# HDMI_RGB_LVDS.net
KiCad netlist of a schematic drawn in EAGLE
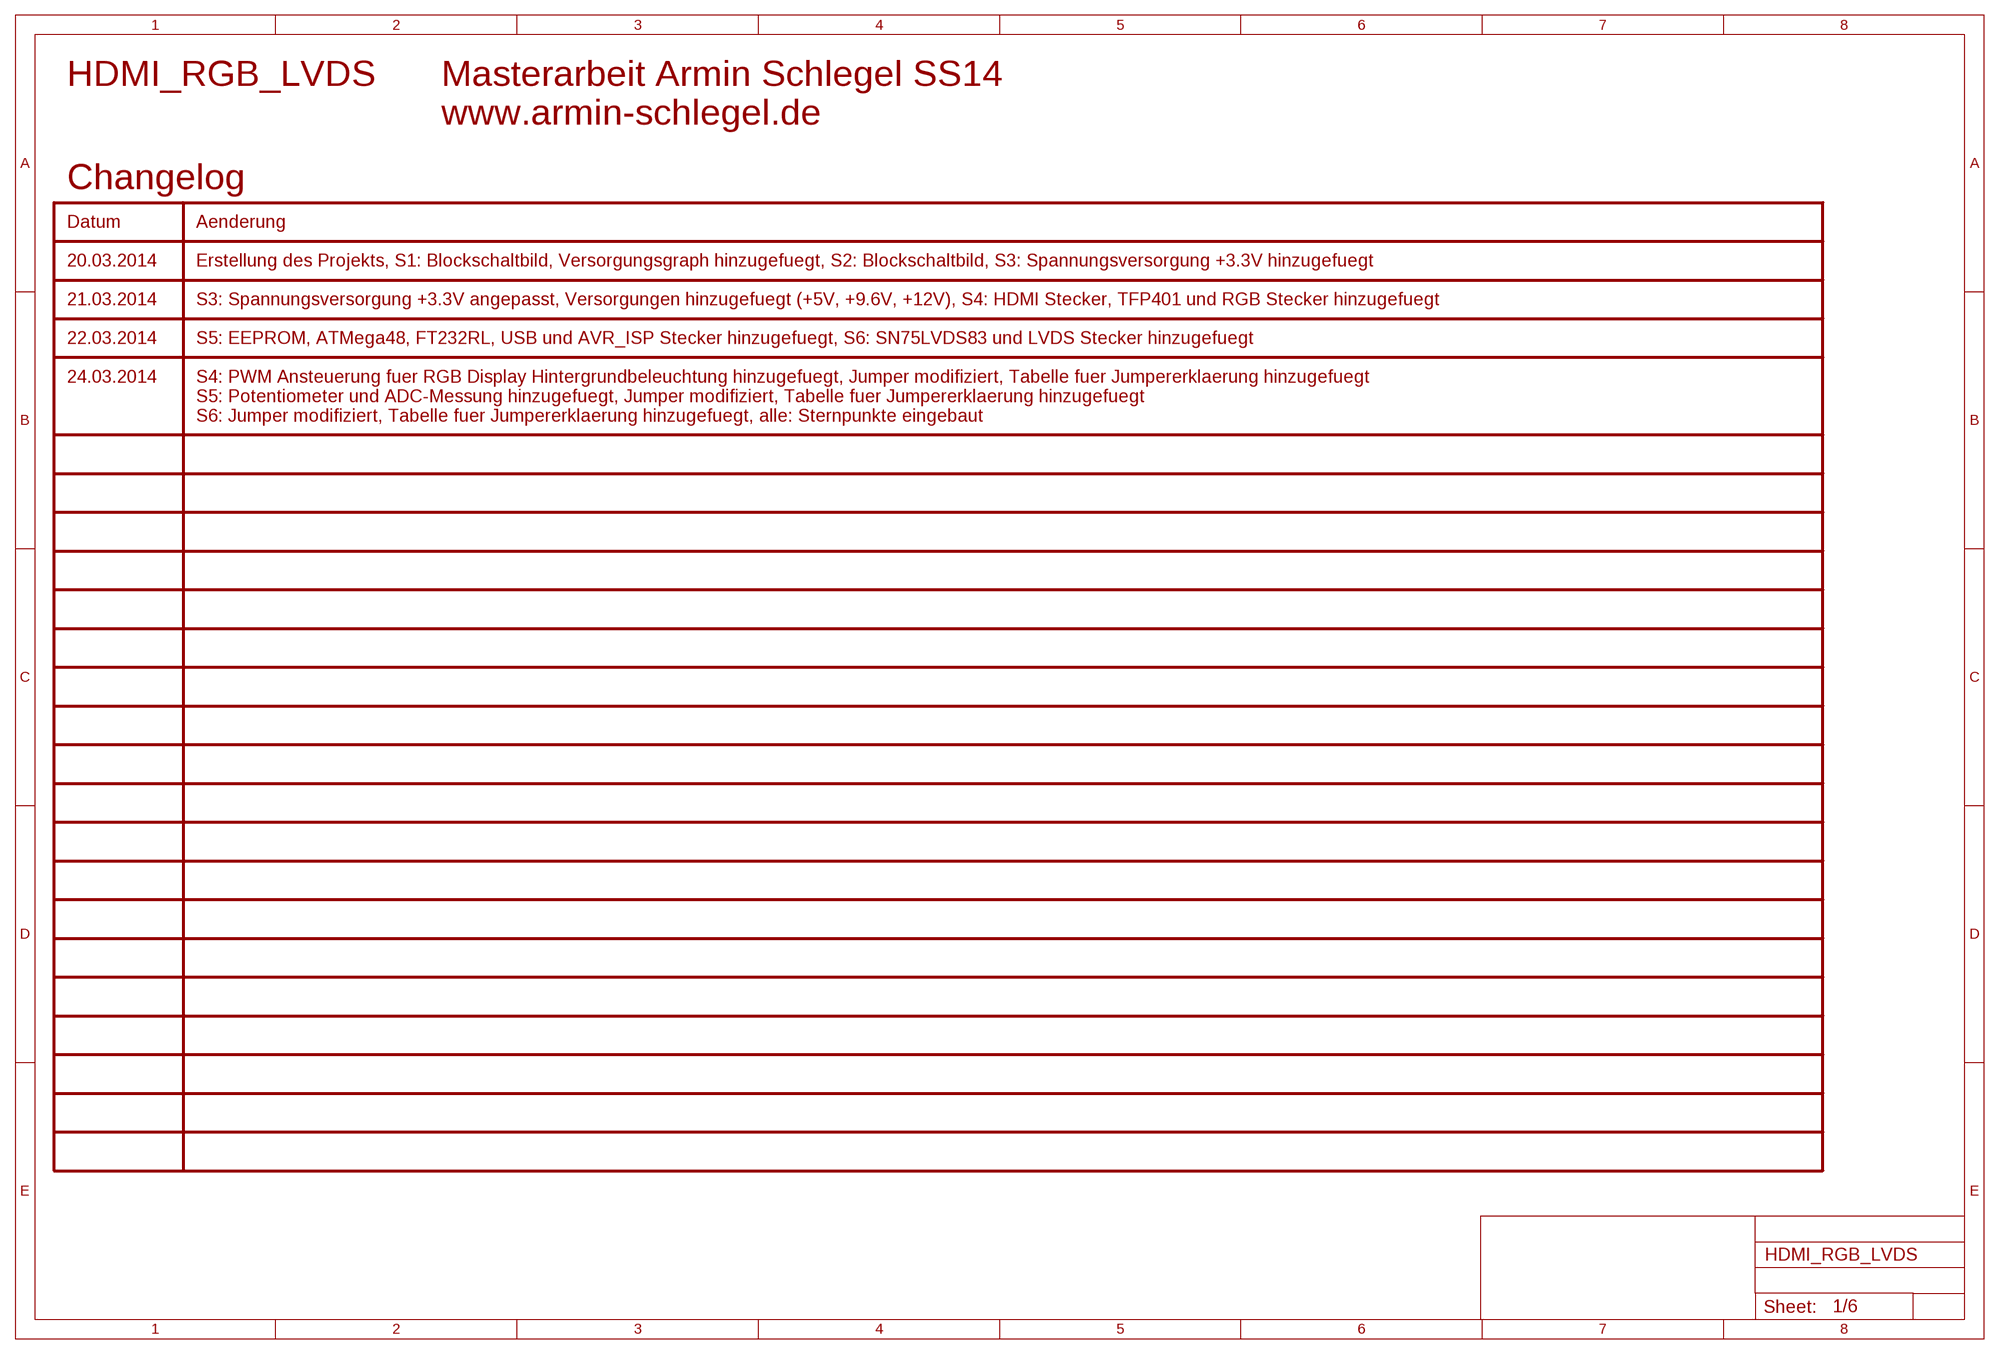
[diagram p0: schematic, sheet 1]
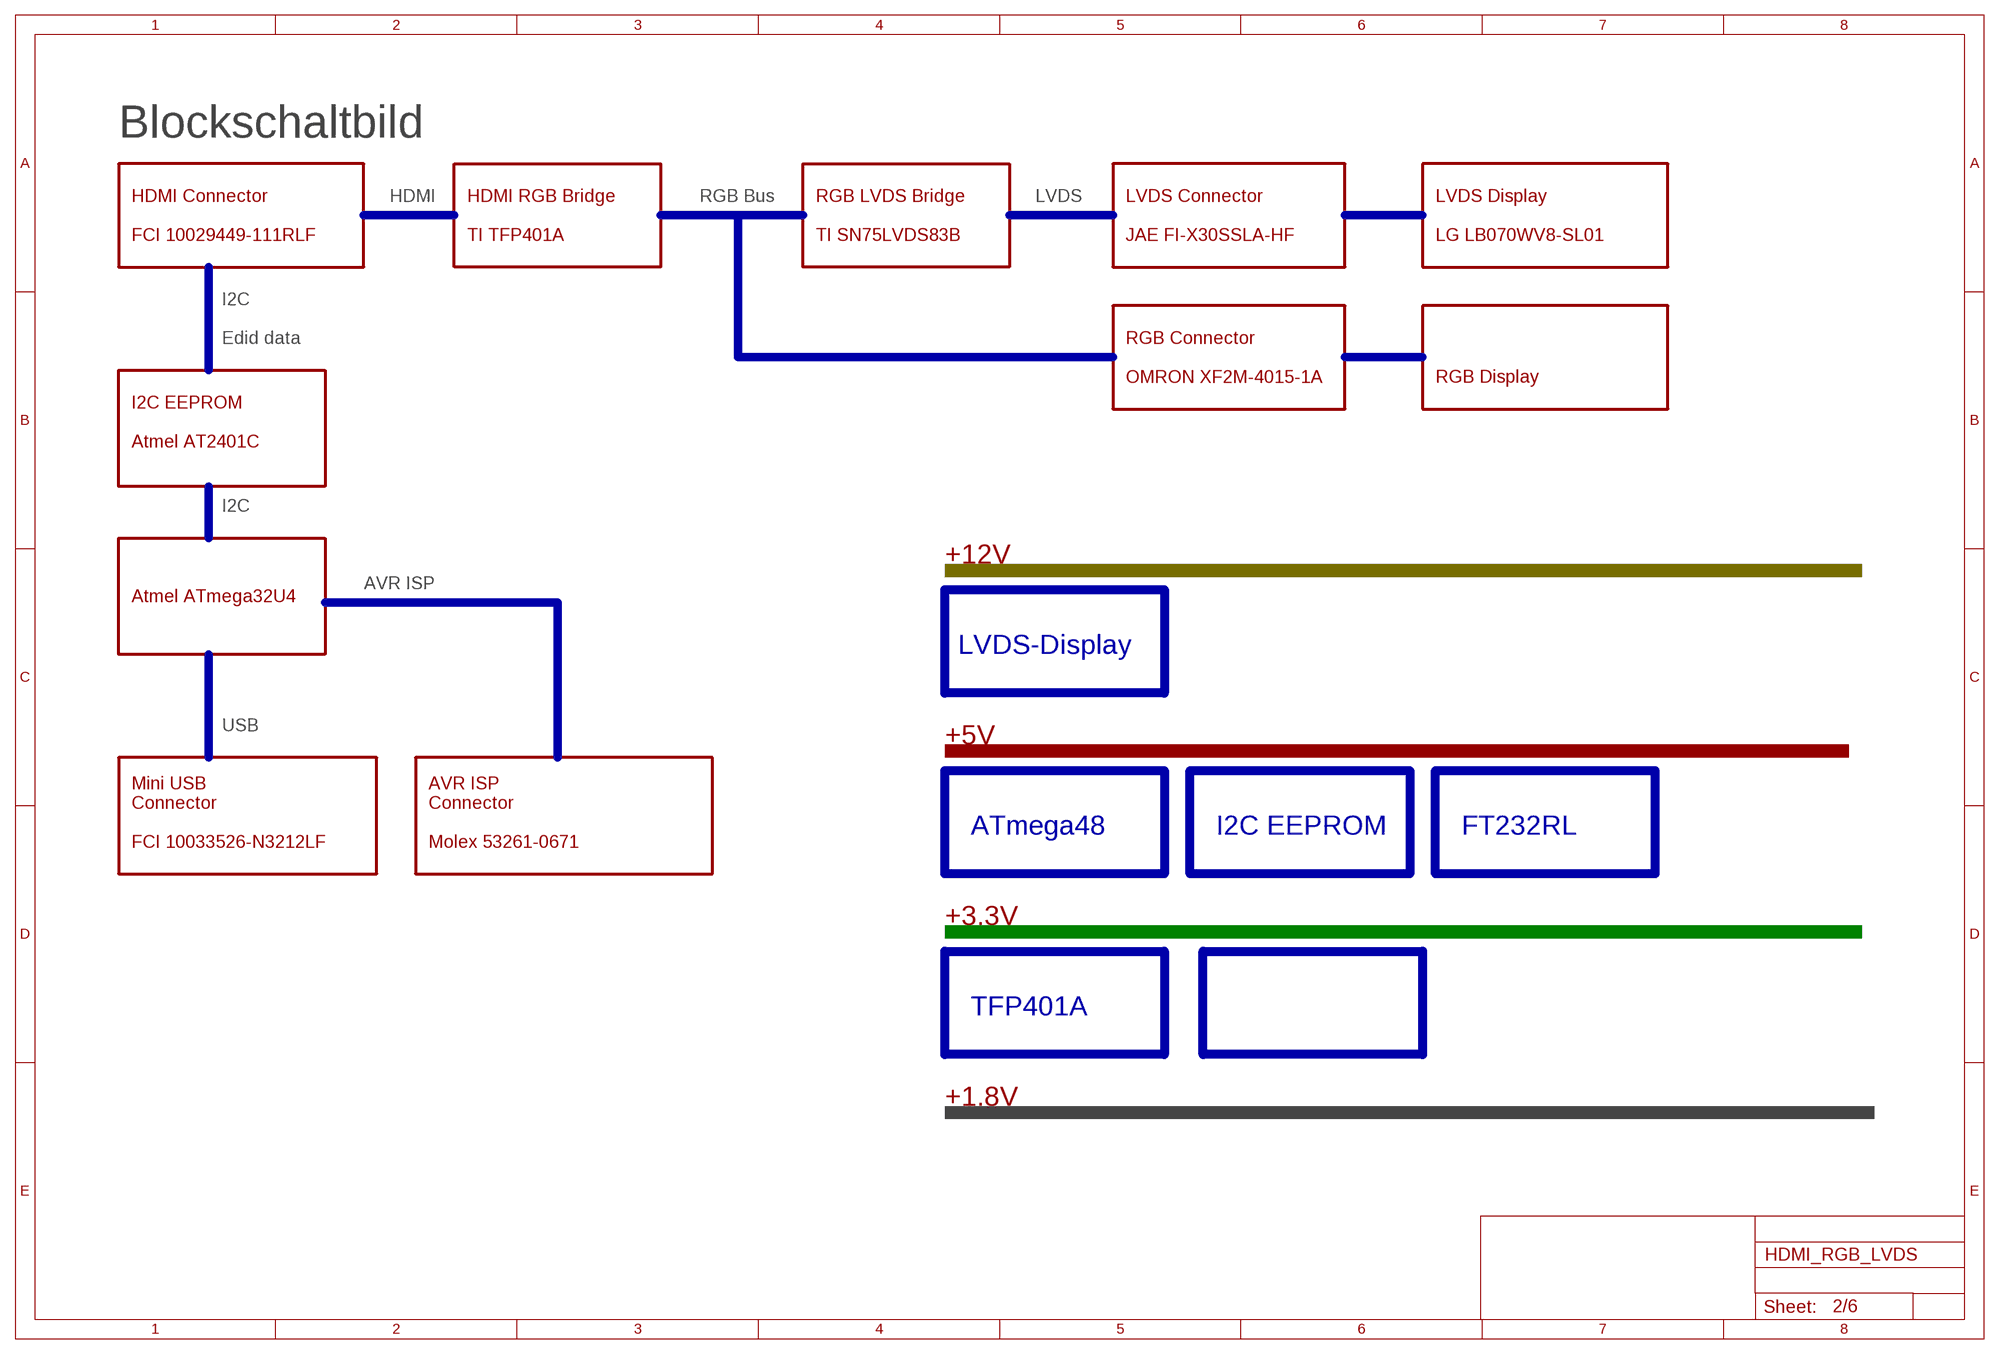
[diagram p1: schematic, sheet 2]
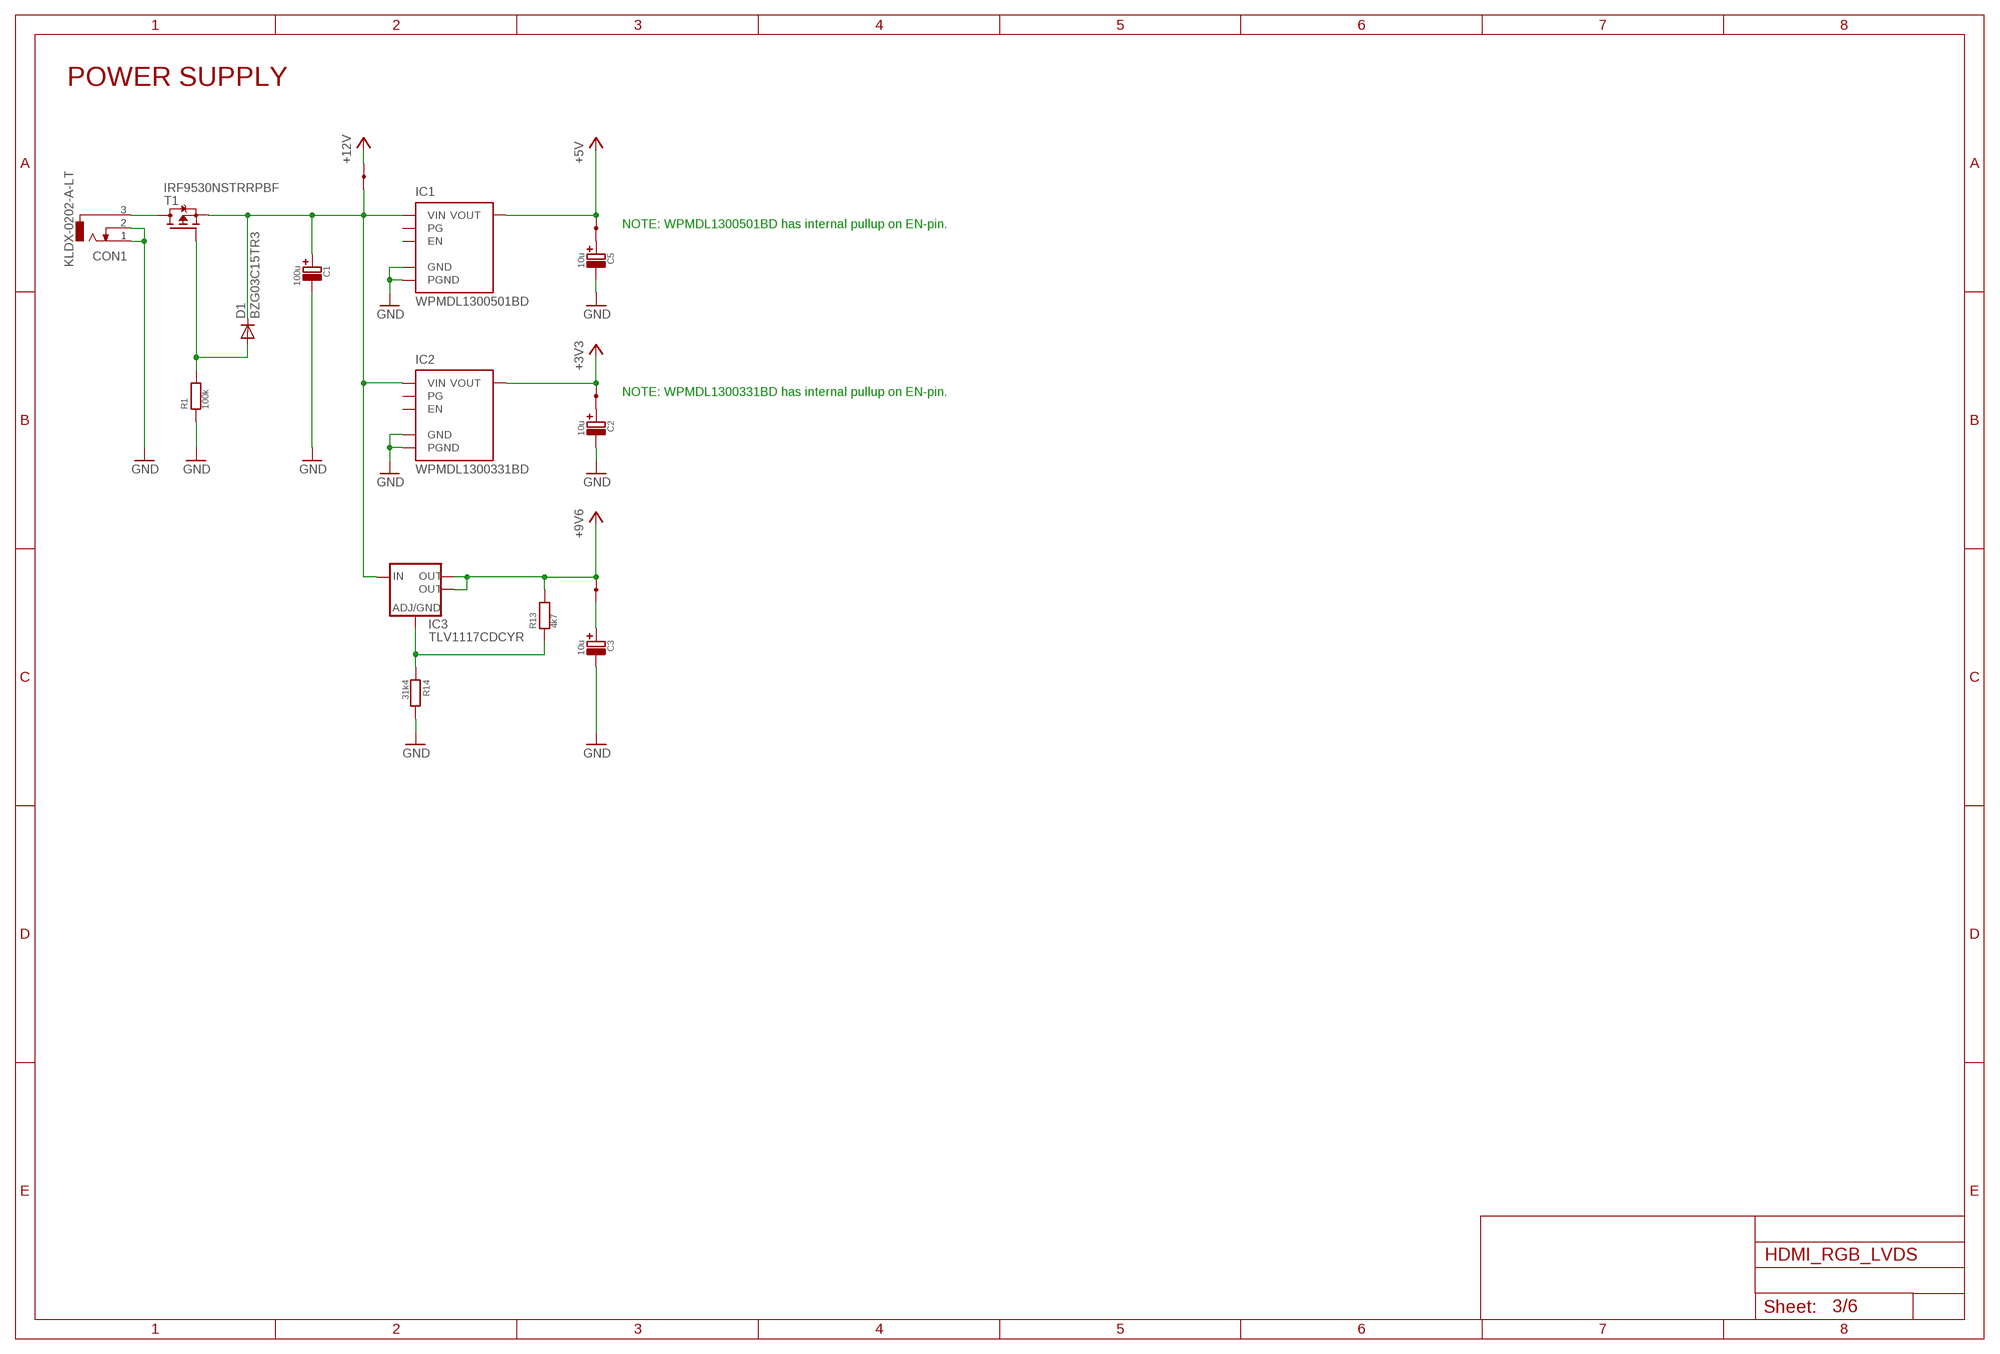
[diagram p2: schematic, sheet 3]
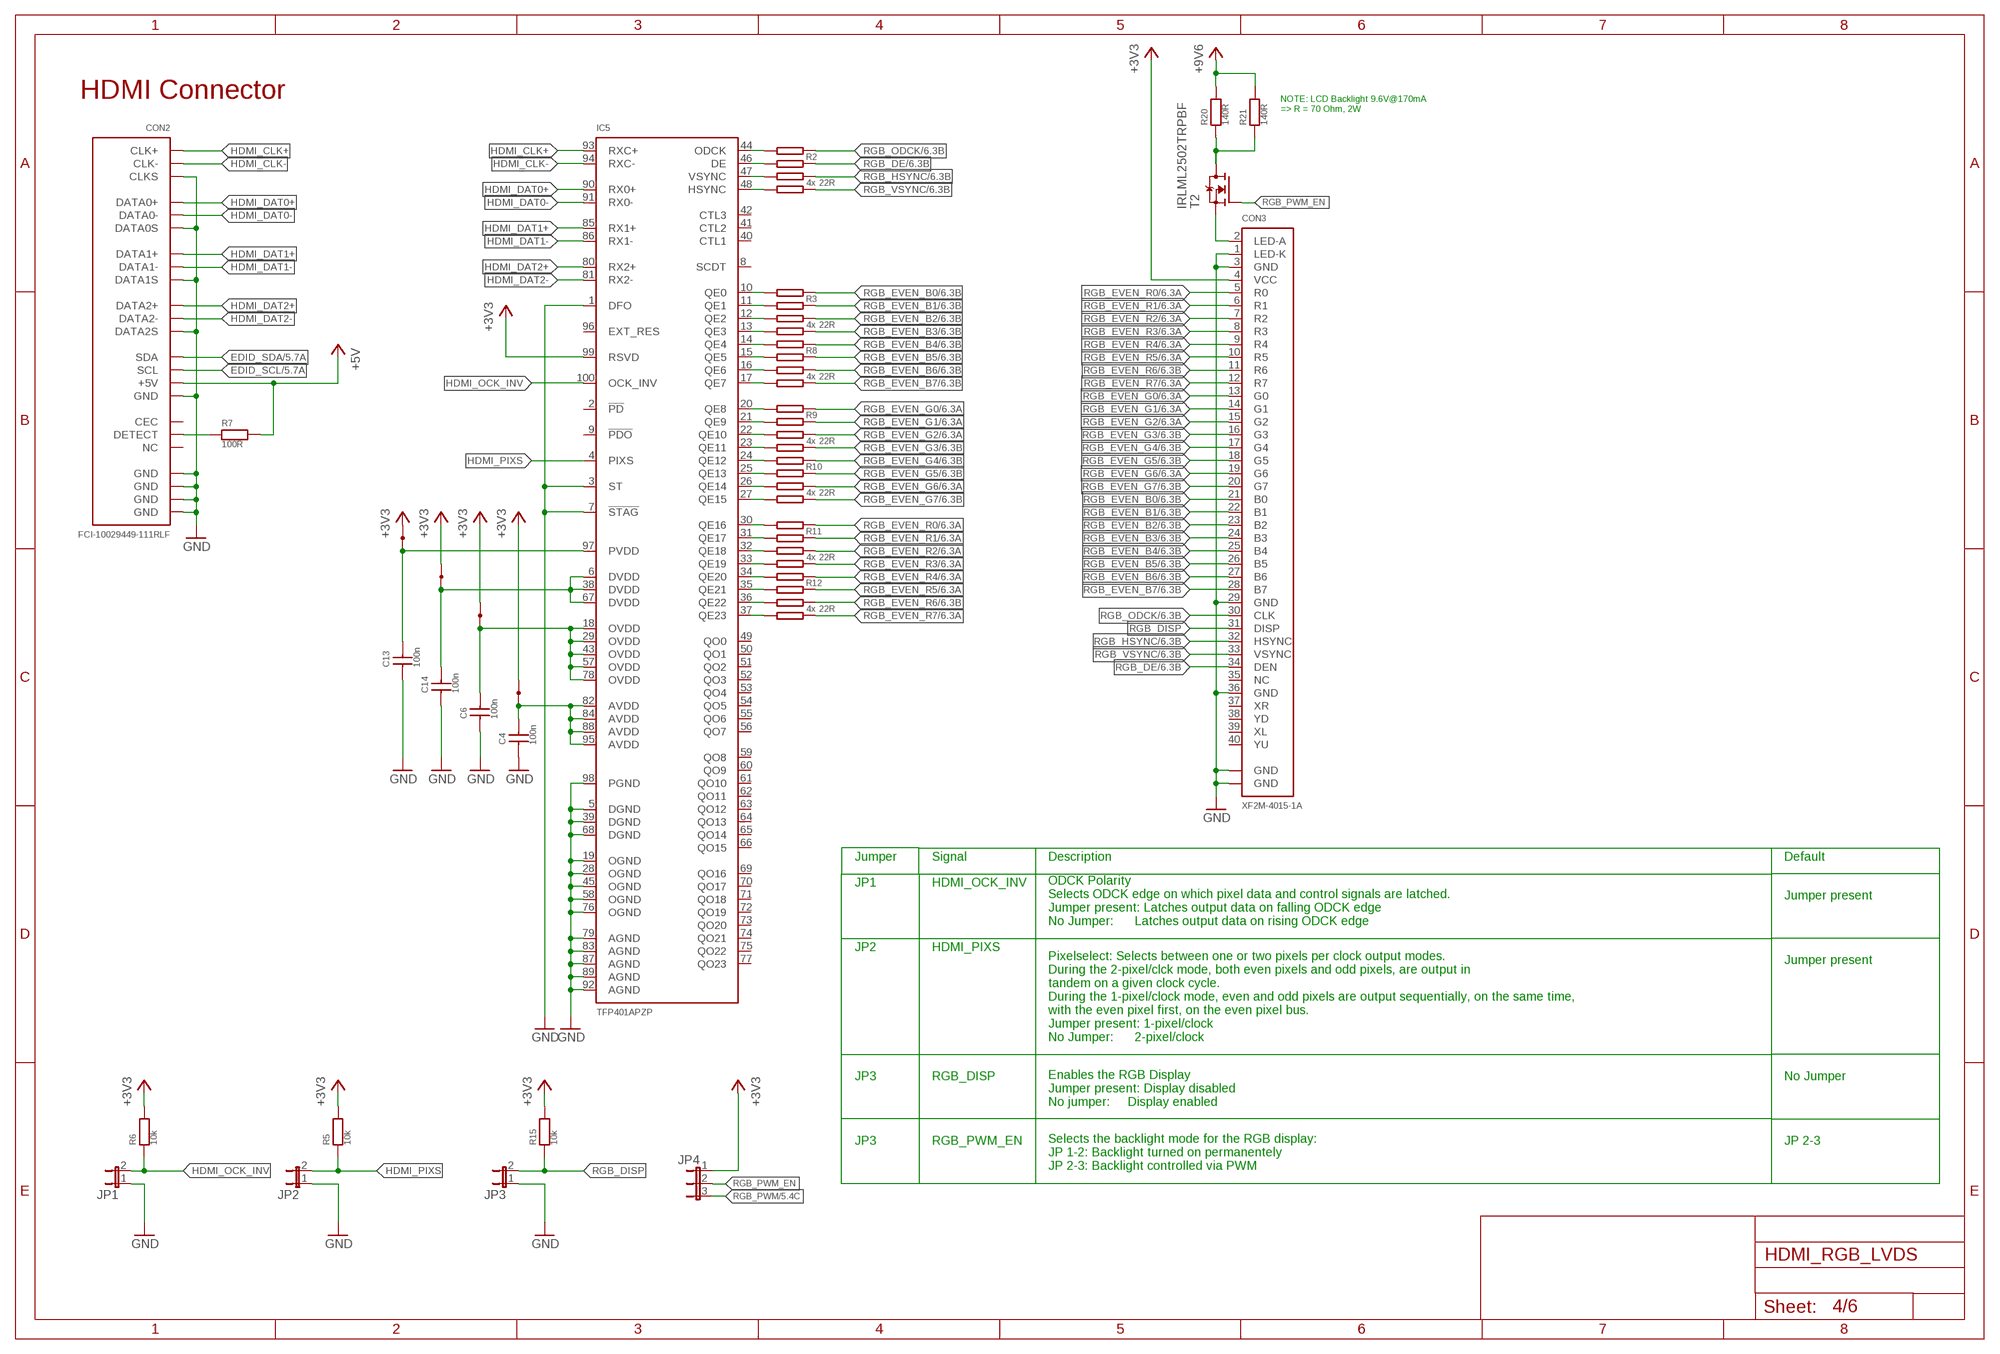
[diagram p3: schematic, sheet 4]
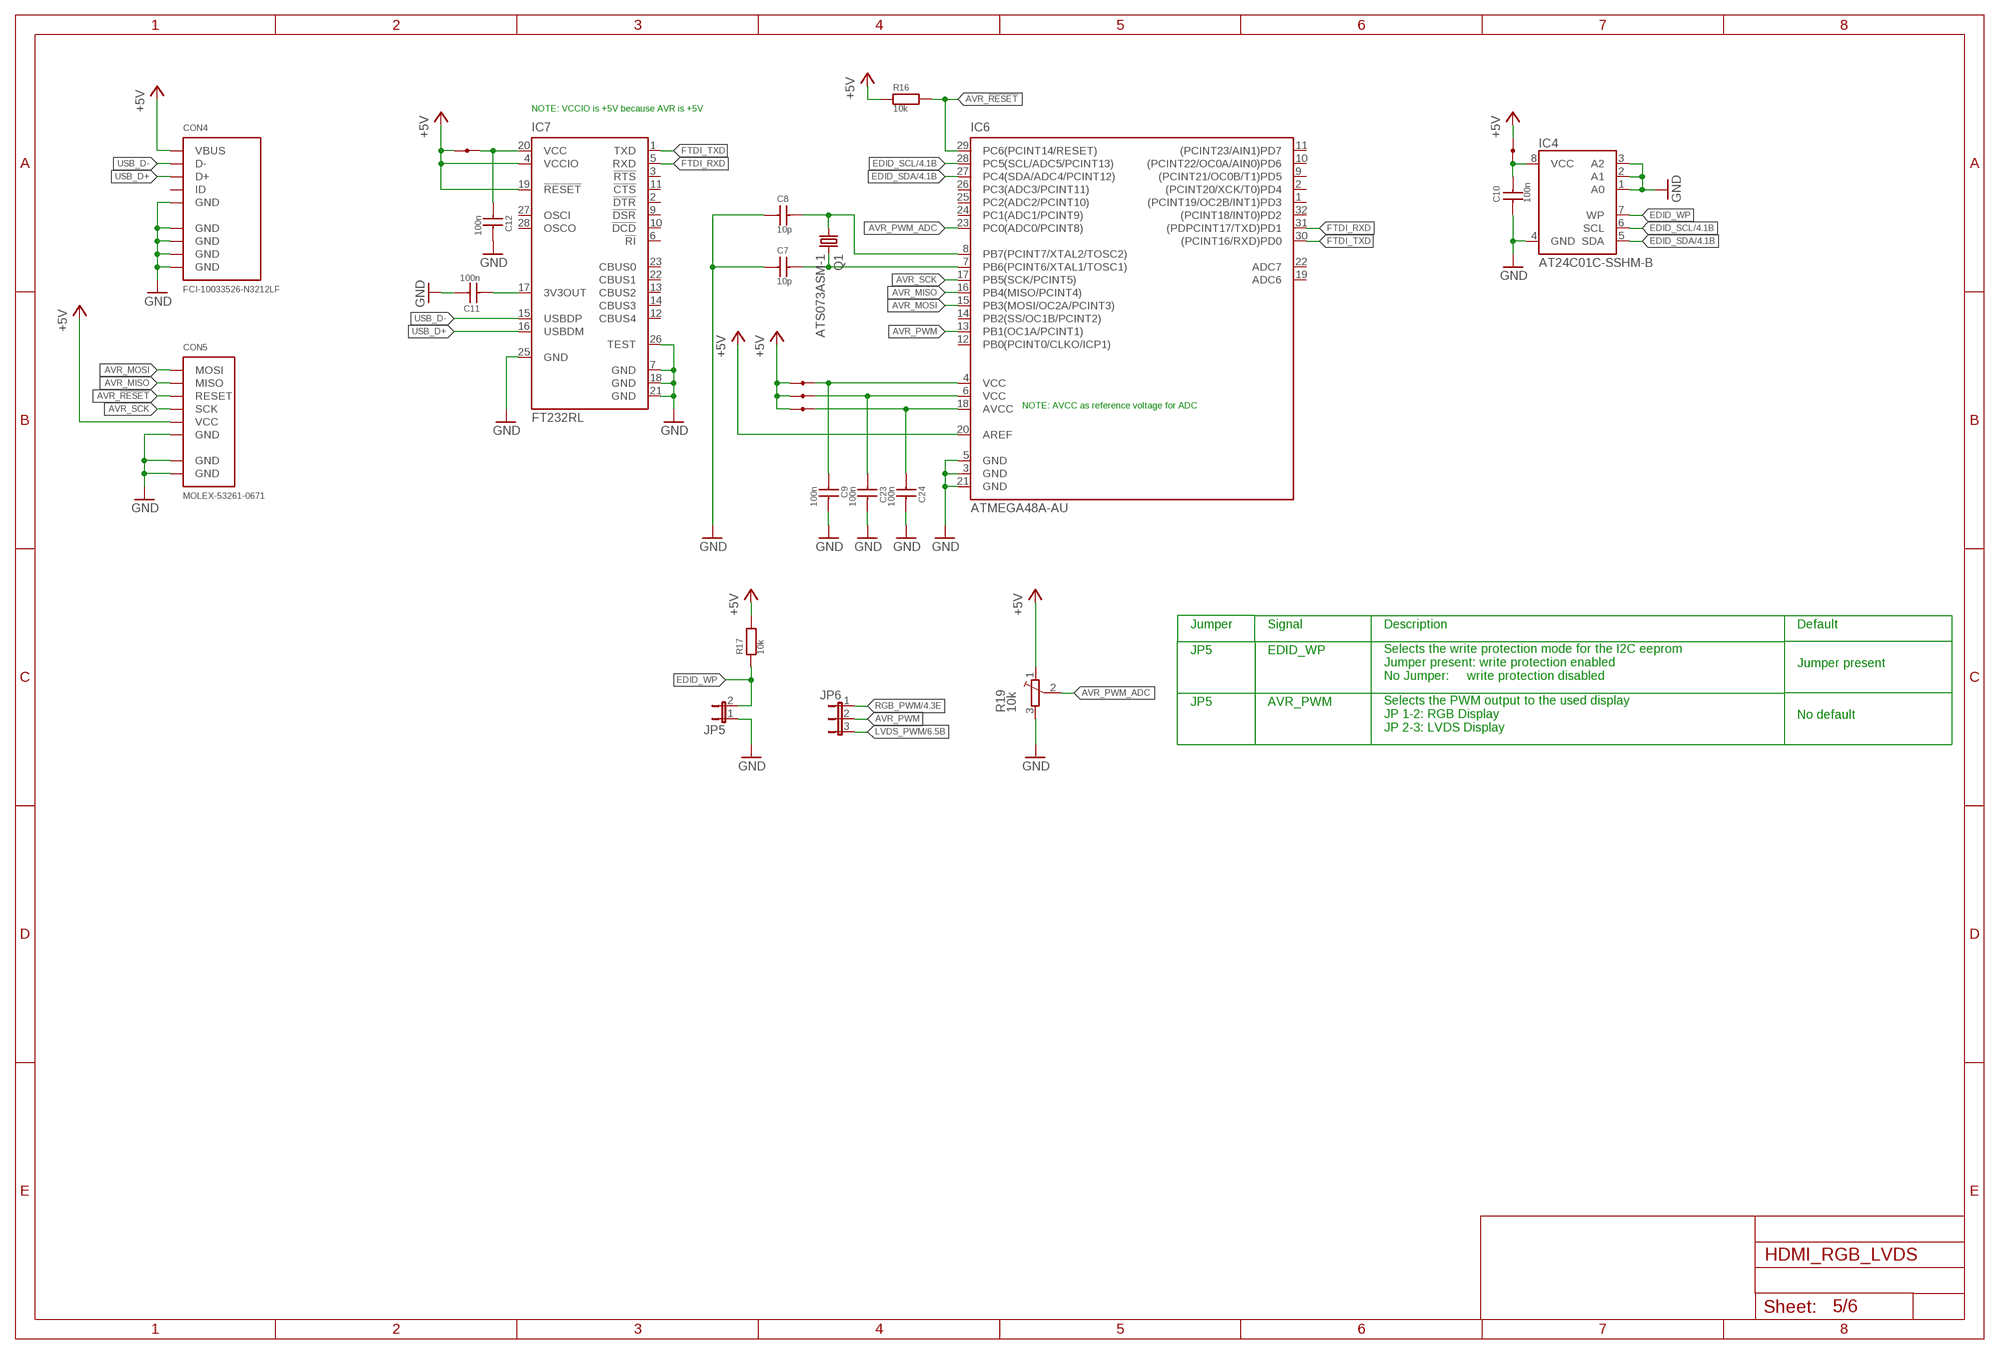
[diagram p4: schematic, sheet 5]
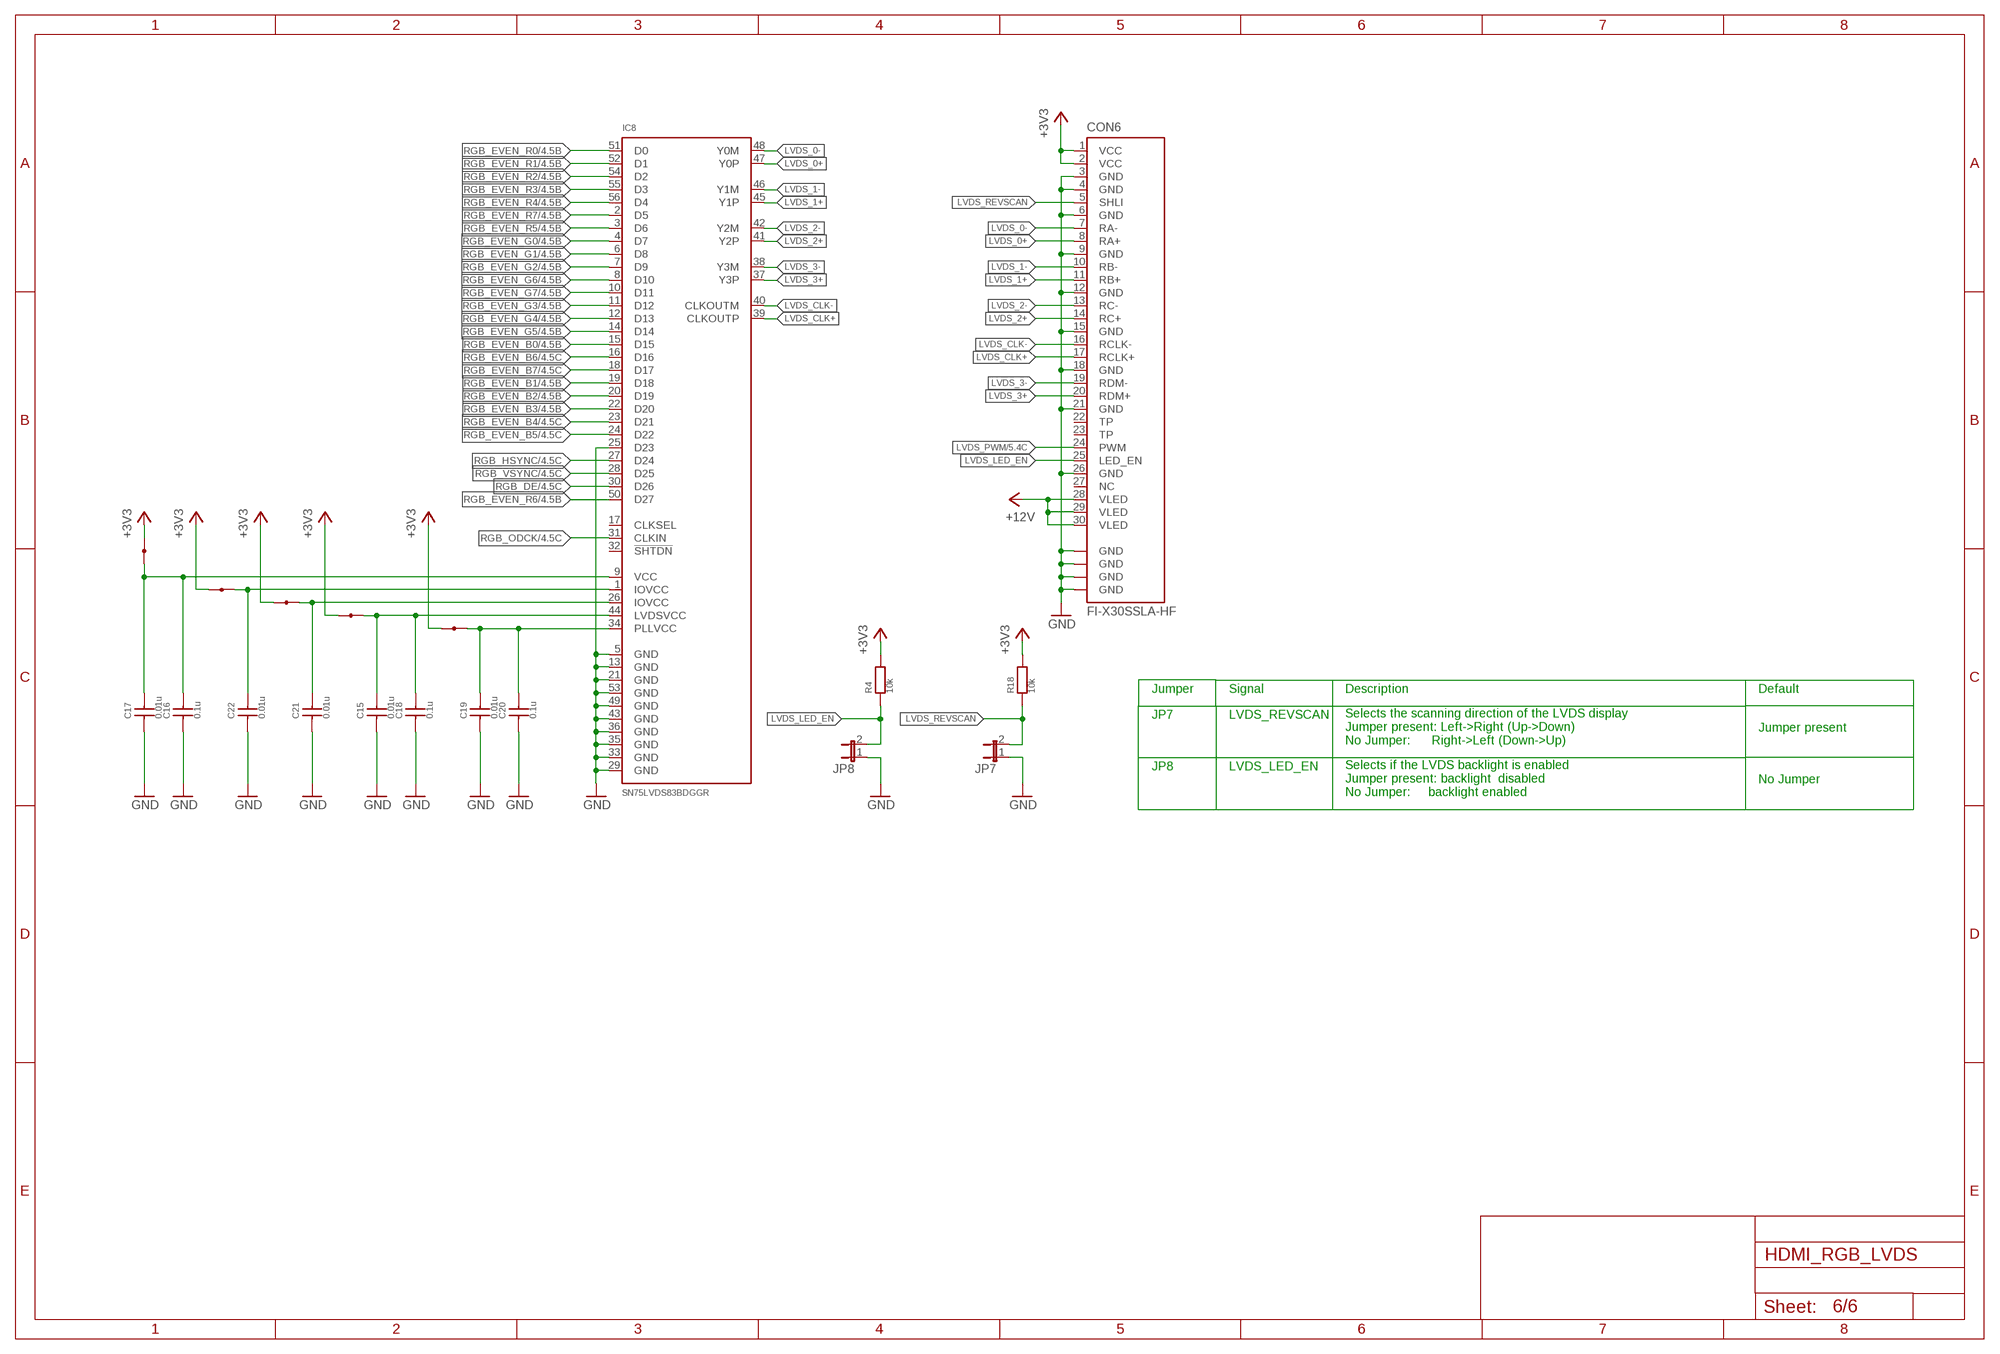
[diagram p5: schematic, sheet 6]

(export (version "E")
  (design (tool "Eeschema 10.0.6"))
  (components
    (comp (ref "U$15")
      (value "FRAME_A3_LANDSCAPE")
      (footprint "eagle-import:FRAME")
      (libsource (lib "eagle-import") (part "FRAME_A3_LANDSCAPE"))
    )
    (comp (ref "C15")
      (value "0.01u")
      (footprint "eagle-import:C0402")
      (libsource (lib "eagle-import") (part "C_SMD0402"))
    )
    (comp (ref "C16")
      (value "0.1u")
      (footprint "eagle-import:C0402")
      (libsource (lib "eagle-import") (part "C_SMD0402"))
    )
    (comp (ref "C17")
      (value "0.01u")
      (footprint "eagle-import:C0402")
      (libsource (lib "eagle-import") (part "C_SMD0402"))
    )
    (comp (ref "C18")
      (value "0.1u")
      (footprint "eagle-import:C0402")
      (libsource (lib "eagle-import") (part "C_SMD0402"))
    )
    (comp (ref "C19")
      (value "0.01u")
      (footprint "eagle-import:C0402")
      (libsource (lib "eagle-import") (part "C_SMD0402"))
    )
    (comp (ref "C20")
      (value "0.1u")
      (footprint "eagle-import:C0402")
      (libsource (lib "eagle-import") (part "C_SMD0402"))
    )
    (comp (ref "C21")
      (value "0.01u")
      (footprint "eagle-import:C0402")
      (libsource (lib "eagle-import") (part "C_SMD0402"))
    )
    (comp (ref "C22")
      (value "0.01u")
      (footprint "eagle-import:C0402")
      (libsource (lib "eagle-import") (part "C_SMD0402"))
    )
    (comp (ref "CON6")
      (value "FI-X30SSLA-HF")
      (footprint "eagle-import:FI-X30SSLA-HF")
      (libsource (lib "eagle-import") (part "FI-X30SSLA-HF"))
    )
    (comp (ref "IC8")
      (value "SN75LVDS83BDGGR")
      (footprint "eagle-import:TSSOP-56")
      (libsource (lib "eagle-import") (part "SN75LVDS83BDGGR"))
    )
    (comp (ref "JP7")
      (value "JUMPER2")
      (footprint "eagle-import:JUMPER2_THROUGHHOLE")
      (libsource (lib "eagle-import") (part "JUMPER2"))
    )
    (comp (ref "JP8")
      (value "JUMPER2")
      (footprint "eagle-import:JUMPER2_THROUGHHOLE")
      (libsource (lib "eagle-import") (part "JUMPER2"))
    )
    (comp (ref "R4")
      (value "10k")
      (footprint "eagle-import:R0402")
      (libsource (lib "eagle-import") (part "R0402"))
    )
    (comp (ref "R18")
      (value "10k")
      (footprint "eagle-import:R0402")
      (libsource (lib "eagle-import") (part "R0402"))
    )
    (comp (ref "SP14")
      (value "SP2")
      (footprint "eagle-import:SP2")
      (libsource (lib "eagle-import") (part "SP2"))
    )
    (comp (ref "SP15")
      (value "SP2")
      (footprint "eagle-import:SP2")
      (libsource (lib "eagle-import") (part "SP2"))
    )
    (comp (ref "SP16")
      (value "SP2")
      (footprint "eagle-import:SP2")
      (libsource (lib "eagle-import") (part "SP2"))
    )
    (comp (ref "SP17")
      (value "SP2")
      (footprint "eagle-import:SP2")
      (libsource (lib "eagle-import") (part "SP2"))
    )
    (comp (ref "SP18")
      (value "SP2")
      (footprint "eagle-import:SP2")
      (libsource (lib "eagle-import") (part "SP2"))
    )
    (comp (ref "U$5")
      (value "FRAME_A3_LANDSCAPE")
      (footprint "eagle-import:FRAME")
      (libsource (lib "eagle-import") (part "FRAME_A3_LANDSCAPE"))
    )
    (comp (ref "C7")
      (value "10p")
      (footprint "eagle-import:C0402")
      (libsource (lib "eagle-import") (part "C_SMD0402"))
    )
    (comp (ref "C8")
      (value "10p")
      (footprint "eagle-import:C0402")
      (libsource (lib "eagle-import") (part "C_SMD0402"))
    )
    (comp (ref "C9")
      (value "100n")
      (footprint "eagle-import:C0402")
      (libsource (lib "eagle-import") (part "C_SMD0402"))
    )
    (comp (ref "C10")
      (value "100n")
      (footprint "eagle-import:C0402")
      (libsource (lib "eagle-import") (part "C_SMD0402"))
    )
    (comp (ref "C11")
      (value "100n")
      (footprint "eagle-import:C0402")
      (libsource (lib "eagle-import") (part "C_SMD0402"))
    )
    (comp (ref "C12")
      (value "100n")
      (footprint "eagle-import:C0402")
      (libsource (lib "eagle-import") (part "C_SMD0402"))
    )
    (comp (ref "C23")
      (value "100n")
      (footprint "eagle-import:C0402")
      (libsource (lib "eagle-import") (part "C_SMD0402"))
    )
    (comp (ref "C24")
      (value "100n")
      (footprint "eagle-import:C0402")
      (libsource (lib "eagle-import") (part "C_SMD0402"))
    )
    (comp (ref "CON4")
      (value "FCI-10033526-N3212LF")
      (footprint "eagle-import:FCI-10033526-N3212LF")
      (libsource (lib "eagle-import") (part "FCI-10033526-N3212LF"))
    )
    (comp (ref "CON5")
      (value "MOLEX-53261-0671")
      (footprint "eagle-import:MOLEX-53261-0671")
      (libsource (lib "eagle-import") (part "MOLEX-53261-0671"))
    )
    (comp (ref "IC4")
      (value "AT24C01C-SSHM-B")
      (footprint "eagle-import:SOIC8")
      (libsource (lib "eagle-import") (part "AT24C01C-SSHM-B"))
    )
    (comp (ref "IC6")
      (value "ATMEGA48A-AU")
      (footprint "eagle-import:TQFP32")
      (libsource (lib "eagle-import") (part "ATMEGA48A-AU"))
    )
    (comp (ref "IC7")
      (value "FT232RL")
      (footprint "eagle-import:SSOP28")
      (libsource (lib "eagle-import") (part "FT232RL"))
    )
    (comp (ref "JP5")
      (value "JUMPER2")
      (footprint "eagle-import:JUMPER2_THROUGHHOLE")
      (libsource (lib "eagle-import") (part "JUMPER2"))
    )
    (comp (ref "JP6")
      (value "JUMPER3")
      (footprint "eagle-import:JUMPER3_THROUGHHOLE")
      (libsource (lib "eagle-import") (part "JUMPER3"))
    )
    (comp (ref "Q1")
      (value "ATS073ASM-1")
      (footprint "eagle-import:HC49_USSM")
      (libsource (lib "eagle-import") (part "ATS073ASM-1"))
    )
    (comp (ref "R16")
      (value "10k")
      (footprint "eagle-import:R0402")
      (libsource (lib "eagle-import") (part "R0402"))
    )
    (comp (ref "R17")
      (value "10k")
      (footprint "eagle-import:R0402")
      (libsource (lib "eagle-import") (part "R0402"))
    )
    (comp (ref "R19")
      (value "10k")
      (footprint "eagle-import:35WR5KLFTR")
      (libsource (lib "eagle-import") (part "35WR5KLFTR"))
    )
    (comp (ref "SP9")
      (value "SP2")
      (footprint "eagle-import:SP2")
      (libsource (lib "eagle-import") (part "SP2"))
    )
    (comp (ref "SP10")
      (value "SP2")
      (footprint "eagle-import:SP2")
      (libsource (lib "eagle-import") (part "SP2"))
    )
    (comp (ref "SP11")
      (value "SP2")
      (footprint "eagle-import:SP2")
      (libsource (lib "eagle-import") (part "SP2"))
    )
    (comp (ref "SP12")
      (value "SP2")
      (footprint "eagle-import:SP2")
      (libsource (lib "eagle-import") (part "SP2"))
    )
    (comp (ref "SP13")
      (value "SP2")
      (footprint "eagle-import:SP2")
      (libsource (lib "eagle-import") (part "SP2"))
    )
    (comp (ref "U$4")
      (value "FRAME_A3_LANDSCAPE")
      (footprint "eagle-import:FRAME")
      (libsource (lib "eagle-import") (part "FRAME_A3_LANDSCAPE"))
    )
    (comp (ref "C1")
      (value "100u")
      (footprint "eagle-import:C_POL_6X6MM")
      (libsource (lib "eagle-import") (part "C_POL6X6MM"))
    )
    (comp (ref "C2")
      (value "10u")
      (footprint "eagle-import:C_POL_4X4MM")
      (libsource (lib "eagle-import") (part "C_POL4X4MM"))
    )
    (comp (ref "C3")
      (value "10u")
      (footprint "eagle-import:C_POL_4X4MM")
      (libsource (lib "eagle-import") (part "C_POL4X4MM"))
    )
    (comp (ref "C5")
      (value "10u")
      (footprint "eagle-import:C_POL_4X4MM")
      (libsource (lib "eagle-import") (part "C_POL4X4MM"))
    )
    (comp (ref "CON1")
      (value "KLDX-0202-A-LT")
      (footprint "eagle-import:KLDX-0202-A-LT")
      (libsource (lib "eagle-import") (part "KLDX-0202-A-LT"))
    )
    (comp (ref "D1")
      (value "BZG03C15TR3")
      (footprint "eagle-import:DO214A")
      (libsource (lib "eagle-import") (part "BZG03C15TR3"))
    )
    (comp (ref "IC1")
      (value "WPMDL1300501BD")
      (footprint "eagle-import:TO263-5")
      (libsource (lib "eagle-import") (part "WPMDL1300501BD"))
    )
    (comp (ref "IC2")
      (value "WPMDL1300331BD")
      (footprint "eagle-import:TO263-5")
      (libsource (lib "eagle-import") (part "WPMDL1300331BD"))
    )
    (comp (ref "IC3")
      (value "TLV1117CDCYR")
      (footprint "eagle-import:SOT223")
      (libsource (lib "eagle-import") (part "TLV1117CDCYR"))
    )
    (comp (ref "R1")
      (value "100k")
      (footprint "eagle-import:R0402")
      (libsource (lib "eagle-import") (part "R0402"))
    )
    (comp (ref "R13")
      (value "4k7")
      (footprint "eagle-import:R0402")
      (libsource (lib "eagle-import") (part "R0402"))
    )
    (comp (ref "R14")
      (value "31k4")
      (footprint "eagle-import:R0402")
      (libsource (lib "eagle-import") (part "R0402"))
    )
    (comp (ref "SP1")
      (value "SP2")
      (footprint "eagle-import:SP2")
      (libsource (lib "eagle-import") (part "SP2"))
    )
    (comp (ref "T1")
      (value "IRF9530NSTRRPBF")
      (footprint "eagle-import:D2PAK")
      (libsource (lib "eagle-import") (part "IRF9530NSTRRPBF"))
    )
    (comp (ref "U$2")
      (value "FRAME_A3_LANDSCAPE")
      (footprint "eagle-import:FRAME")
      (libsource (lib "eagle-import") (part "FRAME_A3_LANDSCAPE"))
    )
    (comp (ref "U$95")
      (value "SP2")
      (footprint "eagle-import:SP2")
      (libsource (lib "eagle-import") (part "SP2"))
    )
    (comp (ref "U$96")
      (value "SP2")
      (footprint "eagle-import:SP2")
      (libsource (lib "eagle-import") (part "SP2"))
    )
    (comp (ref "U$97")
      (value "SP2")
      (footprint "eagle-import:SP2")
      (libsource (lib "eagle-import") (part "SP2"))
    )
    (comp (ref "C4")
      (value "100n")
      (footprint "eagle-import:C0402")
      (libsource (lib "eagle-import") (part "C_SMD0402"))
    )
    (comp (ref "C6")
      (value "100n")
      (footprint "eagle-import:C0402")
      (libsource (lib "eagle-import") (part "C_SMD0402"))
    )
    (comp (ref "C13")
      (value "100n")
      (footprint "eagle-import:C0402")
      (libsource (lib "eagle-import") (part "C_SMD0402"))
    )
    (comp (ref "C14")
      (value "100n")
      (footprint "eagle-import:C0402")
      (libsource (lib "eagle-import") (part "C_SMD0402"))
    )
    (comp (ref "CON2")
      (value "FCI-10029449-111RLF")
      (footprint "eagle-import:FCI-10029449-111RLF")
      (libsource (lib "eagle-import") (part "FCI-10029449-111RLF"))
    )
    (comp (ref "CON3")
      (value "XF2M-4015-1A")
      (footprint "eagle-import:XF2M-4015-1A")
      (libsource (lib "eagle-import") (part "XF2M-4015-1A"))
    )
    (comp (ref "IC5")
      (value "TFP401APZP")
      (footprint "eagle-import:HTQFP-100")
      (libsource (lib "eagle-import") (part "TFP401APZP"))
    )
    (comp (ref "JP1")
      (value "JUMPER2")
      (footprint "eagle-import:JUMPER2_THROUGHHOLE")
      (libsource (lib "eagle-import") (part "JUMPER2"))
    )
    (comp (ref "JP2")
      (value "JUMPER2")
      (footprint "eagle-import:JUMPER2_THROUGHHOLE")
      (libsource (lib "eagle-import") (part "JUMPER2"))
    )
    (comp (ref "JP3")
      (value "JUMPER2")
      (footprint "eagle-import:JUMPER2_THROUGHHOLE")
      (libsource (lib "eagle-import") (part "JUMPER2"))
    )
    (comp (ref "JP4")
      (value "JUMPER3")
      (footprint "eagle-import:JUMPER3_THROUGHHOLE")
      (libsource (lib "eagle-import") (part "JUMPER3"))
    )
    (comp (ref "R2")
      (value "22R")
      (footprint "eagle-import:R-ARRAY-4X0603")
      (libsource (lib "eagle-import") (part "CTR-742C083220JP-4X22R-4X0603"))
    )
    (comp (ref "R3")
      (value "22R")
      (footprint "eagle-import:R-ARRAY-4X0603")
      (libsource (lib "eagle-import") (part "CTR-742C083220JP-4X22R-4X0603"))
    )
    (comp (ref "R5")
      (value "10k")
      (footprint "eagle-import:R0402")
      (libsource (lib "eagle-import") (part "R0402"))
    )
    (comp (ref "R6")
      (value "10k")
      (footprint "eagle-import:R0402")
      (libsource (lib "eagle-import") (part "R0402"))
    )
    (comp (ref "R7")
      (value "100R")
      (footprint "eagle-import:R0402")
      (libsource (lib "eagle-import") (part "R0402"))
    )
    (comp (ref "R8")
      (value "22R")
      (footprint "eagle-import:R-ARRAY-4X0603")
      (libsource (lib "eagle-import") (part "CTR-742C083220JP-4X22R-4X0603"))
    )
    (comp (ref "R9")
      (value "22R")
      (footprint "eagle-import:R-ARRAY-4X0603")
      (libsource (lib "eagle-import") (part "CTR-742C083220JP-4X22R-4X0603"))
    )
    (comp (ref "R10")
      (value "22R")
      (footprint "eagle-import:R-ARRAY-4X0603")
      (libsource (lib "eagle-import") (part "CTR-742C083220JP-4X22R-4X0603"))
    )
    (comp (ref "R11")
      (value "22R")
      (footprint "eagle-import:R-ARRAY-4X0603")
      (libsource (lib "eagle-import") (part "CTR-742C083220JP-4X22R-4X0603"))
    )
    (comp (ref "R12")
      (value "22R")
      (footprint "eagle-import:R-ARRAY-4X0603")
      (libsource (lib "eagle-import") (part "CTR-742C083220JP-4X22R-4X0603"))
    )
    (comp (ref "R15")
      (value "10k")
      (footprint "eagle-import:R0402")
      (libsource (lib "eagle-import") (part "R0402"))
    )
    (comp (ref "R20")
      (value "140R")
      (footprint "eagle-import:R2512")
      (libsource (lib "eagle-import") (part "R2512"))
    )
    (comp (ref "R21")
      (value "140R")
      (footprint "eagle-import:R2512")
      (libsource (lib "eagle-import") (part "R2512"))
    )
    (comp (ref "SP2")
      (value "SP2")
      (footprint "eagle-import:SP2")
      (libsource (lib "eagle-import") (part "SP2"))
    )
    (comp (ref "SP3")
      (value "SP2")
      (footprint "eagle-import:SP2")
      (libsource (lib "eagle-import") (part "SP2"))
    )
    (comp (ref "SP4")
      (value "SP2")
      (footprint "eagle-import:SP2")
      (libsource (lib "eagle-import") (part "SP2"))
    )
    (comp (ref "SP5")
      (value "SP2")
      (footprint "eagle-import:SP2")
      (libsource (lib "eagle-import") (part "SP2"))
    )
    (comp (ref "T2")
      (value "IRLML2502TRPBF")
      (footprint "eagle-import:SOT23")
      (libsource (lib "eagle-import") (part "IRLML2502TRPBF"))
    )
    (comp (ref "U$3")
      (value "FRAME_A3_LANDSCAPE")
      (footprint "eagle-import:FRAME")
      (libsource (lib "eagle-import") (part "FRAME_A3_LANDSCAPE"))
    )
    (comp (ref "U$1")
      (value "FRAME_A3_LANDSCAPE")
      (footprint "eagle-import:FRAME")
      (libsource (lib "eagle-import") (part "FRAME_A3_LANDSCAPE"))
    )
  )
  (nets
    (net (code "2") (name "+3V3") (class "Default")
      (node (ref "CON3") (pin "4") (pinfunction "VCC_4") (pintype "bidirectional"))
      (node (ref "CON6") (pin "1") (pinfunction "VCC_1") (pintype "bidirectional"))
      (node (ref "CON6") (pin "2") (pinfunction "VCC_2") (pintype "bidirectional"))
      (node (ref "IC2") (pin "3") (pinfunction "VOUT_3") (pintype "bidirectional"))
      (node (ref "IC5") (pin "99") (pinfunction "RSVD_99") (pintype "bidirectional"))
      (node (ref "JP4") (pin "1") (pinfunction "1_1") (pintype "passive"))
      (node (ref "R15") (pin "2") (pinfunction "P$2_2") (pintype "passive"))
      (node (ref "R18") (pin "2") (pinfunction "P$2_2") (pintype "passive"))
      (node (ref "R4") (pin "2") (pinfunction "P$2_2") (pintype "passive"))
      (node (ref "R5") (pin "2") (pinfunction "P$2_2") (pintype "passive"))
      (node (ref "R6") (pin "2") (pinfunction "P$2_2") (pintype "passive"))
      (node (ref "SP14") (pin "P$2") (pinfunction "2_P$2") (pintype "bidirectional"))
      (node (ref "SP15") (pin "P$2") (pinfunction "2_P$2") (pintype "bidirectional"))
      (node (ref "SP16") (pin "P$2") (pinfunction "2_P$2") (pintype "bidirectional"))
      (node (ref "SP17") (pin "P$2") (pinfunction "2_P$2") (pintype "bidirectional"))
      (node (ref "SP18") (pin "P$2") (pinfunction "2_P$2") (pintype "bidirectional"))
      (node (ref "SP2") (pin "P$2") (pinfunction "2_P$2") (pintype "bidirectional"))
      (node (ref "SP3") (pin "P$2") (pinfunction "2_P$2") (pintype "bidirectional"))
      (node (ref "SP4") (pin "P$2") (pinfunction "2_P$2") (pintype "bidirectional"))
      (node (ref "SP5") (pin "P$2") (pinfunction "2_P$2") (pintype "bidirectional"))
      (node (ref "U$96") (pin "P$2") (pinfunction "2_P$2") (pintype "bidirectional"))
    )
    (net (code "3") (name "+5V") (class "Default")
      (node (ref "CON2") (pin "18") (pinfunction "+5V_18") (pintype "bidirectional"))
      (node (ref "CON4") (pin "1") (pinfunction "VBUS_1") (pintype "bidirectional"))
      (node (ref "CON5") (pin "5") (pinfunction "VCC_5") (pintype "bidirectional"))
      (node (ref "IC1") (pin "3") (pinfunction "VOUT_3") (pintype "bidirectional"))
      (node (ref "IC6") (pin "20") (pinfunction "AREF_20") (pintype "power_in"))
      (node (ref "IC7") (pin "19") (pinfunction "~{RESET}_19") (pintype "input"))
      (node (ref "IC7") (pin "4") (pinfunction "VCCIO_4") (pintype "power_in"))
      (node (ref "R16") (pin "1") (pinfunction "P$1_1") (pintype "passive"))
      (node (ref "R17") (pin "2") (pinfunction "P$2_2") (pintype "passive"))
      (node (ref "R19") (pin "1") (pinfunction "E_1") (pintype "passive"))
      (node (ref "R7") (pin "2") (pinfunction "P$2_2") (pintype "passive"))
      (node (ref "SP10") (pin "P$1") (pinfunction "1_P$1") (pintype "bidirectional"))
      (node (ref "SP11") (pin "P$1") (pinfunction "1_P$1") (pintype "bidirectional"))
      (node (ref "SP12") (pin "P$1") (pinfunction "1_P$1") (pintype "bidirectional"))
      (node (ref "SP13") (pin "P$1") (pinfunction "1_P$1") (pintype "bidirectional"))
      (node (ref "SP9") (pin "P$2") (pinfunction "2_P$2") (pintype "bidirectional"))
      (node (ref "U$95") (pin "P$2") (pinfunction "2_P$2") (pintype "bidirectional"))
    )
    (net (code "4") (name "+9V6") (class "Default")
      (node (ref "IC3") (pin "2") (pinfunction "OUT_2") (pintype "passive"))
      (node (ref "IC3") (pin "4") (pinfunction "OUT1_4") (pintype "passive"))
      (node (ref "R13") (pin "2") (pinfunction "P$2_2") (pintype "passive"))
      (node (ref "R20") (pin "2") (pinfunction "P$2_2") (pintype "passive"))
      (node (ref "R21") (pin "2") (pinfunction "P$2_2") (pintype "passive"))
      (node (ref "U$97") (pin "P$2") (pinfunction "2_P$2") (pintype "bidirectional"))
    )
    (net (code "5") (name "+12V") (class "Default")
      (node (ref "CON6") (pin "28") (pinfunction "VLED_28") (pintype "bidirectional"))
      (node (ref "CON6") (pin "29") (pinfunction "VLED_29") (pintype "bidirectional"))
      (node (ref "CON6") (pin "30") (pinfunction "VLED_30") (pintype "bidirectional"))
      (node (ref "SP1") (pin "P$2") (pinfunction "2_P$2") (pintype "bidirectional"))
    )
    (net (code "7") (name "AVR_MISO") (class "Default")
      (node (ref "CON5") (pin "2") (pinfunction "MISO_2") (pintype "bidirectional"))
      (node (ref "IC6") (pin "16") (pinfunction "PB4(MISO/PCINT4)_16") (pintype "bidirectional"))
    )
    (net (code "8") (name "AVR_MOSI") (class "Default")
      (node (ref "CON5") (pin "1") (pinfunction "MOSI_1") (pintype "bidirectional"))
      (node (ref "IC6") (pin "15") (pinfunction "PB3(MOSI/OC2A/PCINT3)_15") (pintype "bidirectional"))
    )
    (net (code "9") (name "AVR_PWM") (class "Default")
      (node (ref "IC6") (pin "13") (pinfunction "PB1(OC1A/PCINT1)_13") (pintype "bidirectional"))
      (node (ref "JP6") (pin "2") (pinfunction "2_2") (pintype "passive"))
    )
    (net (code "10") (name "AVR_PWM_ADC") (class "Default")
      (node (ref "IC6") (pin "23") (pinfunction "PC0(ADC0/PCINT8)_23") (pintype "bidirectional"))
      (node (ref "R19") (pin "2") (pinfunction "S_2") (pintype "passive"))
    )
    (net (code "11") (name "AVR_SCK") (class "Default")
      (node (ref "CON5") (pin "4") (pinfunction "SCK_4") (pintype "bidirectional"))
      (node (ref "IC6") (pin "17") (pinfunction "PB5(SCK/PCINT5)_17") (pintype "bidirectional"))
    )
    (net (code "12") (name "AVR_~{RESET}") (class "Default")
      (node (ref "CON5") (pin "3") (pinfunction "RESET_3") (pintype "bidirectional"))
      (node (ref "IC6") (pin "29") (pinfunction "PC6(PCINT14/RESET)_29") (pintype "bidirectional"))
      (node (ref "R16") (pin "2") (pinfunction "P$2_2") (pintype "passive"))
    )
    (net (code "13") (name "EDID_SCL") (class "Default")
      (node (ref "CON2") (pin "15") (pinfunction "SCL_15") (pintype "bidirectional"))
      (node (ref "IC4") (pin "6") (pinfunction "SCL_6") (pintype "bidirectional"))
      (node (ref "IC6") (pin "28") (pinfunction "PC5(SCL/ADC5/PCINT13)_28") (pintype "bidirectional"))
    )
    (net (code "14") (name "EDID_SDA") (class "Default")
      (node (ref "CON2") (pin "16") (pinfunction "SDA_16") (pintype "bidirectional"))
      (node (ref "IC4") (pin "5") (pinfunction "SDA_5") (pintype "bidirectional"))
      (node (ref "IC6") (pin "27") (pinfunction "PC4(SDA/ADC4/PCINT12)_27") (pintype "bidirectional"))
    )
    (net (code "15") (name "EDID_WP") (class "Default")
      (node (ref "IC4") (pin "7") (pinfunction "WP_7") (pintype "input"))
      (node (ref "JP5") (pin "2") (pinfunction "2_2") (pintype "passive"))
      (node (ref "R17") (pin "1") (pinfunction "P$1_1") (pintype "passive"))
    )
    (net (code "16") (name "FTDI_RXD") (class "Default")
      (node (ref "IC6") (pin "31") (pinfunction "(PDPCINT17/TXD)PD1_31") (pintype "bidirectional"))
      (node (ref "IC7") (pin "5") (pinfunction "RXD_5") (pintype "input"))
    )
    (net (code "17") (name "FTDI_TXD") (class "Default")
      (node (ref "IC6") (pin "30") (pinfunction "(PCINT16/RXD)PD0_30") (pintype "bidirectional"))
      (node (ref "IC7") (pin "1") (pinfunction "TXD_1") (pintype "output"))
    )
    (net (code "18") (name "GND") (class "Default")
      (node (ref "C1") (pin "-") (pinfunction "P$2_-") (pintype "passive"))
      (node (ref "C10") (pin "1") (pinfunction "P$1_1") (pintype "passive"))
      (node (ref "C11") (pin "2") (pinfunction "P$2_2") (pintype "passive"))
      (node (ref "C12") (pin "2") (pinfunction "P$2_2") (pintype "passive"))
      (node (ref "C13") (pin "1") (pinfunction "P$1_1") (pintype "passive"))
      (node (ref "C14") (pin "1") (pinfunction "P$1_1") (pintype "passive"))
      (node (ref "C15") (pin "1") (pinfunction "P$1_1") (pintype "passive"))
      (node (ref "C16") (pin "1") (pinfunction "P$1_1") (pintype "passive"))
      (node (ref "C17") (pin "1") (pinfunction "P$1_1") (pintype "passive"))
      (node (ref "C18") (pin "1") (pinfunction "P$1_1") (pintype "passive"))
      (node (ref "C19") (pin "1") (pinfunction "P$1_1") (pintype "passive"))
      (node (ref "C2") (pin "-") (pinfunction "P$2_-") (pintype "passive"))
      (node (ref "C20") (pin "1") (pinfunction "P$1_1") (pintype "passive"))
      (node (ref "C21") (pin "1") (pinfunction "P$1_1") (pintype "passive"))
      (node (ref "C22") (pin "1") (pinfunction "P$1_1") (pintype "passive"))
      (node (ref "C23") (pin "2") (pinfunction "P$2_2") (pintype "passive"))
      (node (ref "C24") (pin "2") (pinfunction "P$2_2") (pintype "passive"))
      (node (ref "C3") (pin "-") (pinfunction "P$2_-") (pintype "passive"))
      (node (ref "C4") (pin "1") (pinfunction "P$1_1") (pintype "passive"))
      (node (ref "C5") (pin "-") (pinfunction "P$2_-") (pintype "passive"))
      (node (ref "C6") (pin "1") (pinfunction "P$1_1") (pintype "passive"))
      (node (ref "C7") (pin "1") (pinfunction "P$1_1") (pintype "passive"))
      (node (ref "C8") (pin "1") (pinfunction "P$1_1") (pintype "passive"))
      (node (ref "C9") (pin "2") (pinfunction "P$2_2") (pintype "passive"))
      (node (ref "CON1") (pin "1") (pinfunction "3_1") (pintype "passive"))
      (node (ref "CON1") (pin "2") (pinfunction "2_2") (pintype "passive"))
      (node (ref "CON2") (pin "11") (pinfunction "CLKS_11") (pintype "bidirectional"))
      (node (ref "CON2") (pin "17") (pinfunction "GND_17") (pintype "bidirectional"))
      (node (ref "CON2") (pin "2") (pinfunction "DATA2S_2") (pintype "bidirectional"))
      (node (ref "CON2") (pin "5") (pinfunction "DATA1S_5") (pintype "bidirectional"))
      (node (ref "CON2") (pin "8") (pinfunction "DATA0S_8") (pintype "bidirectional"))
      (node (ref "CON2") (pin "GND@1") (pinfunction "GND_GND@1") (pintype "power_in"))
      (node (ref "CON2") (pin "GND@2") (pinfunction "GND_GND@2") (pintype "power_in"))
      (node (ref "CON2") (pin "GND@3") (pinfunction "GND_GND@3") (pintype "power_in"))
      (node (ref "CON2") (pin "GND@4") (pinfunction "GND_GND@4") (pintype "power_in"))
      (node (ref "CON3") (pin "1") (pinfunction "LED-K_1") (pintype "bidirectional"))
      (node (ref "CON3") (pin "29") (pinfunction "GND_29") (pintype "bidirectional"))
      (node (ref "CON3") (pin "3") (pinfunction "GND_3") (pintype "bidirectional"))
      (node (ref "CON3") (pin "36") (pinfunction "GND_36") (pintype "bidirectional"))
      (node (ref "CON3") (pin "GND@1") (pinfunction "GND_GND@1") (pintype "power_in"))
      (node (ref "CON3") (pin "GND@2") (pinfunction "GND_GND@2") (pintype "power_in"))
      (node (ref "CON4") (pin "5") (pinfunction "GND_5") (pintype "bidirectional"))
      (node (ref "CON4") (pin "GND@1") (pinfunction "GND_GND@1") (pintype "power_in"))
      (node (ref "CON4") (pin "GND@2") (pinfunction "GND_GND@2") (pintype "power_in"))
      (node (ref "CON4") (pin "GND@3") (pinfunction "GND_GND@3") (pintype "power_in"))
      (node (ref "CON4") (pin "GND@4") (pinfunction "GND_GND@4") (pintype "power_in"))
      (node (ref "CON5") (pin "6") (pinfunction "GND_6") (pintype "bidirectional"))
      (node (ref "CON5") (pin "GND@1") (pinfunction "GND_GND@1") (pintype "power_in"))
      (node (ref "CON5") (pin "GND@2") (pinfunction "GND_GND@2") (pintype "power_in"))
      (node (ref "CON6") (pin "12") (pinfunction "GND_12") (pintype "bidirectional"))
      (node (ref "CON6") (pin "15") (pinfunction "GND_15") (pintype "bidirectional"))
      (node (ref "CON6") (pin "18") (pinfunction "GND_18") (pintype "bidirectional"))
      (node (ref "CON6") (pin "21") (pinfunction "GND_21") (pintype "bidirectional"))
      (node (ref "CON6") (pin "26") (pinfunction "GND_26") (pintype "bidirectional"))
      (node (ref "CON6") (pin "3") (pinfunction "GND_3") (pintype "bidirectional"))
      (node (ref "CON6") (pin "4") (pinfunction "GND_4") (pintype "bidirectional"))
      (node (ref "CON6") (pin "6") (pinfunction "GND_6") (pintype "bidirectional"))
      (node (ref "CON6") (pin "9") (pinfunction "GND_9") (pintype "bidirectional"))
      (node (ref "CON6") (pin "GND@1") (pinfunction "GND_GND@1") (pintype "power_in"))
      (node (ref "CON6") (pin "GND@2") (pinfunction "GND_GND@2") (pintype "power_in"))
      (node (ref "CON6") (pin "GND@3") (pinfunction "GND_GND@3") (pintype "power_in"))
      (node (ref "CON6") (pin "GND@4") (pinfunction "GND_GND@4") (pintype "power_in"))
      (node (ref "IC1") (pin "2") (pinfunction "GND_2") (pintype "bidirectional"))
      (node (ref "IC1") (pin "6") (pinfunction "PGND_6") (pintype "bidirectional"))
      (node (ref "IC2") (pin "2") (pinfunction "GND_2") (pintype "bidirectional"))
      (node (ref "IC2") (pin "6") (pinfunction "PGND_6") (pintype "bidirectional"))
      (node (ref "IC4") (pin "1") (pinfunction "A0_1") (pintype "input"))
      (node (ref "IC4") (pin "2") (pinfunction "A1_2") (pintype "input"))
      (node (ref "IC4") (pin "3") (pinfunction "A2_3") (pintype "input"))
      (node (ref "IC4") (pin "4") (pinfunction "GND_4") (pintype "power_in"))
      (node (ref "IC5") (pin "1") (pinfunction "DFO_1") (pintype "bidirectional"))
      (node (ref "IC5") (pin "19") (pinfunction "OGND_19") (pintype "power_in"))
      (node (ref "IC5") (pin "28") (pinfunction "OGND_28") (pintype "power_in"))
      (node (ref "IC5") (pin "3") (pinfunction "ST_3") (pintype "bidirectional"))
      (node (ref "IC5") (pin "39") (pinfunction "DGND_39") (pintype "power_in"))
      (node (ref "IC5") (pin "45") (pinfunction "OGND_45") (pintype "power_in"))
      (node (ref "IC5") (pin "5") (pinfunction "DGND_5") (pintype "power_in"))
      (node (ref "IC5") (pin "58") (pinfunction "OGND_58") (pintype "power_in"))
      (node (ref "IC5") (pin "68") (pinfunction "DGND_68") (pintype "power_in"))
      (node (ref "IC5") (pin "7") (pinfunction "~{STAG}_7") (pintype "bidirectional"))
      (node (ref "IC5") (pin "76") (pinfunction "OGND_76") (pintype "power_in"))
      (node (ref "IC5") (pin "79") (pinfunction "AGND_79") (pintype "power_in"))
      (node (ref "IC5") (pin "83") (pinfunction "AGND_83") (pintype "power_in"))
      (node (ref "IC5") (pin "87") (pinfunction "AGND_87") (pintype "power_in"))
      (node (ref "IC5") (pin "89") (pinfunction "AGND_89") (pintype "power_in"))
      (node (ref "IC5") (pin "92") (pinfunction "AGND_92") (pintype "power_in"))
      (node (ref "IC5") (pin "98") (pinfunction "PGND_98") (pintype "power_in"))
      (node (ref "IC6") (pin "21") (pinfunction "GND_21") (pintype "power_in"))
      (node (ref "IC6") (pin "3") (pinfunction "GND_3") (pintype "power_in"))
      (node (ref "IC6") (pin "5") (pinfunction "GND_5") (pintype "power_in"))
      (node (ref "IC7") (pin "18") (pinfunction "GND_18") (pintype "power_in"))
      (node (ref "IC7") (pin "21") (pinfunction "GND_21") (pintype "power_in"))
      (node (ref "IC7") (pin "25") (pinfunction "GND_25") (pintype "power_in"))
      (node (ref "IC7") (pin "26") (pinfunction "TEST_26") (pintype "input"))
      (node (ref "IC7") (pin "7") (pinfunction "GND_7") (pintype "power_in"))
      (node (ref "IC8") (pin "13") (pinfunction "GND_13") (pintype "power_in"))
      (node (ref "IC8") (pin "21") (pinfunction "GND_21") (pintype "power_in"))
      (node (ref "IC8") (pin "25") (pinfunction "D23_25") (pintype "bidirectional"))
      (node (ref "IC8") (pin "29") (pinfunction "GND_29") (pintype "power_in"))
      (node (ref "IC8") (pin "33") (pinfunction "GND_33") (pintype "power_in"))
      (node (ref "IC8") (pin "35") (pinfunction "GND_35") (pintype "power_in"))
      (node (ref "IC8") (pin "36") (pinfunction "GND_36") (pintype "power_in"))
      (node (ref "IC8") (pin "43") (pinfunction "GND_43") (pintype "power_in"))
      (node (ref "IC8") (pin "49") (pinfunction "GND_49") (pintype "power_in"))
      (node (ref "IC8") (pin "5") (pinfunction "GND_5") (pintype "power_in"))
      (node (ref "IC8") (pin "53") (pinfunction "GND_53") (pintype "power_in"))
      (node (ref "JP1") (pin "1") (pinfunction "1_1") (pintype "passive"))
      (node (ref "JP2") (pin "1") (pinfunction "1_1") (pintype "passive"))
      (node (ref "JP3") (pin "1") (pinfunction "1_1") (pintype "passive"))
      (node (ref "JP5") (pin "1") (pinfunction "1_1") (pintype "passive"))
      (node (ref "JP7") (pin "1") (pinfunction "1_1") (pintype "passive"))
      (node (ref "JP8") (pin "1") (pinfunction "1_1") (pintype "passive"))
      (node (ref "R1") (pin "1") (pinfunction "P$1_1") (pintype "passive"))
      (node (ref "R14") (pin "2") (pinfunction "P$2_2") (pintype "passive"))
      (node (ref "R19") (pin "3") (pinfunction "A_3") (pintype "passive"))
    )
    (net (code "19") (name "HDMI_CLK+") (class "Default")
      (node (ref "CON2") (pin "10") (pinfunction "CLK+_10") (pintype "bidirectional"))
      (node (ref "IC5") (pin "93") (pinfunction "RXC+_93") (pintype "bidirectional"))
    )
    (net (code "20") (name "HDMI_CLK-") (class "Default")
      (node (ref "CON2") (pin "12") (pinfunction "CLK-_12") (pintype "bidirectional"))
      (node (ref "IC5") (pin "94") (pinfunction "RXC-_94") (pintype "bidirectional"))
    )
    (net (code "21") (name "HDMI_DAT0+") (class "Default")
      (node (ref "CON2") (pin "7") (pinfunction "DATA0+_7") (pintype "bidirectional"))
      (node (ref "IC5") (pin "90") (pinfunction "RX0+_90") (pintype "bidirectional"))
    )
    (net (code "22") (name "HDMI_DAT0-") (class "Default")
      (node (ref "CON2") (pin "9") (pinfunction "DATA0-_9") (pintype "bidirectional"))
      (node (ref "IC5") (pin "91") (pinfunction "RX0-_91") (pintype "bidirectional"))
    )
    (net (code "23") (name "HDMI_DAT1+") (class "Default")
      (node (ref "CON2") (pin "4") (pinfunction "DATA1+_4") (pintype "bidirectional"))
      (node (ref "IC5") (pin "85") (pinfunction "RX1+_85") (pintype "bidirectional"))
    )
    (net (code "24") (name "HDMI_DAT1-") (class "Default")
      (node (ref "CON2") (pin "6") (pinfunction "DATA1-_6") (pintype "bidirectional"))
      (node (ref "IC5") (pin "86") (pinfunction "RX1-_86") (pintype "bidirectional"))
    )
    (net (code "25") (name "HDMI_DAT2+") (class "Default")
      (node (ref "CON2") (pin "1") (pinfunction "DATA2+_1") (pintype "bidirectional"))
      (node (ref "IC5") (pin "80") (pinfunction "RX2+_80") (pintype "bidirectional"))
    )
    (net (code "26") (name "HDMI_DAT2-") (class "Default")
      (node (ref "CON2") (pin "3") (pinfunction "DATA2-_3") (pintype "bidirectional"))
      (node (ref "IC5") (pin "81") (pinfunction "RX2-_81") (pintype "bidirectional"))
    )
    (net (code "27") (name "HDMI_OCK_INV") (class "Default")
      (node (ref "IC5") (pin "100") (pinfunction "OCK_INV_100") (pintype "bidirectional"))
      (node (ref "JP1") (pin "2") (pinfunction "2_2") (pintype "passive"))
      (node (ref "R6") (pin "1") (pinfunction "P$1_1") (pintype "passive"))
    )
    (net (code "28") (name "HDMI_PIXS") (class "Default")
      (node (ref "IC5") (pin "4") (pinfunction "PIXS_4") (pintype "bidirectional"))
      (node (ref "JP2") (pin "2") (pinfunction "2_2") (pintype "passive"))
      (node (ref "R5") (pin "1") (pinfunction "P$1_1") (pintype "passive"))
    )
    (net (code "29") (name "LVDS_0+") (class "Default")
      (node (ref "CON6") (pin "8") (pinfunction "RA+_8") (pintype "bidirectional"))
      (node (ref "IC8") (pin "47") (pinfunction "Y0P_47") (pintype "bidirectional"))
    )
    (net (code "30") (name "LVDS_0-") (class "Default")
      (node (ref "CON6") (pin "7") (pinfunction "RA-_7") (pintype "bidirectional"))
      (node (ref "IC8") (pin "48") (pinfunction "Y0M_48") (pintype "bidirectional"))
    )
    (net (code "31") (name "LVDS_1+") (class "Default")
      (node (ref "CON6") (pin "11") (pinfunction "RB+_11") (pintype "bidirectional"))
      (node (ref "IC8") (pin "45") (pinfunction "Y1P_45") (pintype "bidirectional"))
    )
    (net (code "32") (name "LVDS_1-") (class "Default")
      (node (ref "CON6") (pin "10") (pinfunction "RB-_10") (pintype "bidirectional"))
      (node (ref "IC8") (pin "46") (pinfunction "Y1M_46") (pintype "bidirectional"))
    )
    (net (code "33") (name "LVDS_2+") (class "Default")
      (node (ref "CON6") (pin "14") (pinfunction "RC+_14") (pintype "bidirectional"))
      (node (ref "IC8") (pin "41") (pinfunction "Y2P_41") (pintype "bidirectional"))
    )
    (net (code "34") (name "LVDS_2-") (class "Default")
      (node (ref "CON6") (pin "13") (pinfunction "RC-_13") (pintype "bidirectional"))
      (node (ref "IC8") (pin "42") (pinfunction "Y2M_42") (pintype "bidirectional"))
    )
    (net (code "35") (name "LVDS_3+") (class "Default")
      (node (ref "CON6") (pin "20") (pinfunction "RDM+_20") (pintype "bidirectional"))
      (node (ref "IC8") (pin "37") (pinfunction "Y3P_37") (pintype "bidirectional"))
    )
    (net (code "36") (name "LVDS_3-") (class "Default")
      (node (ref "CON6") (pin "19") (pinfunction "RDM-_19") (pintype "bidirectional"))
      (node (ref "IC8") (pin "38") (pinfunction "Y3M_38") (pintype "bidirectional"))
    )
    (net (code "37") (name "LVDS_CLK+") (class "Default")
      (node (ref "CON6") (pin "17") (pinfunction "RCLK+_17") (pintype "bidirectional"))
      (node (ref "IC8") (pin "39") (pinfunction "CLKOUTP_39") (pintype "bidirectional"))
    )
    (net (code "38") (name "LVDS_CLK-") (class "Default")
      (node (ref "CON6") (pin "16") (pinfunction "RCLK-_16") (pintype "bidirectional"))
      (node (ref "IC8") (pin "40") (pinfunction "CLKOUTM_40") (pintype "bidirectional"))
    )
    (net (code "39") (name "LVDS_LED_EN") (class "Default")
      (node (ref "CON6") (pin "25") (pinfunction "LED_EN_25") (pintype "bidirectional"))
      (node (ref "JP8") (pin "2") (pinfunction "2_2") (pintype "passive"))
      (node (ref "R4") (pin "1") (pinfunction "P$1_1") (pintype "passive"))
    )
    (net (code "40") (name "LVDS_PWM") (class "Default")
      (node (ref "CON6") (pin "24") (pinfunction "PWM_24") (pintype "bidirectional"))
      (node (ref "JP6") (pin "3") (pinfunction "3_3") (pintype "passive"))
    )
    (net (code "41") (name "LVDS_REVSCAN") (class "Default")
      (node (ref "CON6") (pin "5") (pinfunction "SHLI_5") (pintype "bidirectional"))
      (node (ref "JP7") (pin "2") (pinfunction "2_2") (pintype "passive"))
      (node (ref "R18") (pin "1") (pinfunction "P$1_1") (pintype "passive"))
    )
    (net (code "42") (name "Net-(C1-P$1)") (class "Default")
      (node (ref "C1") (pin "+") (pinfunction "P$1_+") (pintype "passive"))
      (node (ref "D1") (pin "C") (pinfunction "C_C") (pintype "passive"))
      (node (ref "IC1") (pin "1") (pinfunction "VIN_1") (pintype "bidirectional"))
      (node (ref "IC2") (pin "1") (pinfunction "VIN_1") (pintype "bidirectional"))
      (node (ref "IC3") (pin "3") (pinfunction "IN_3") (pintype "input"))
      (node (ref "SP1") (pin "P$1") (pinfunction "1_P$1") (pintype "bidirectional"))
      (node (ref "T1") (pin "3") (pinfunction "S_3") (pintype "passive"))
    )
    (net (code "43") (name "Net-(C2-P$1)") (class "Default")
      (node (ref "C2") (pin "+") (pinfunction "P$1_+") (pintype "passive"))
      (node (ref "U$96") (pin "P$1") (pinfunction "1_P$1") (pintype "bidirectional"))
    )
    (net (code "44") (name "Net-(C3-P$1)") (class "Default")
      (node (ref "C3") (pin "+") (pinfunction "P$1_+") (pintype "passive"))
      (node (ref "U$97") (pin "P$1") (pinfunction "1_P$1") (pintype "bidirectional"))
    )
    (net (code "45") (name "Net-(C4-P$2)") (class "Default")
      (node (ref "C4") (pin "2") (pinfunction "P$2_2") (pintype "passive"))
      (node (ref "IC5") (pin "82") (pinfunction "AVDD_82") (pintype "power_in"))
      (node (ref "IC5") (pin "84") (pinfunction "AVDD_84") (pintype "power_in"))
      (node (ref "IC5") (pin "88") (pinfunction "AVDD_88") (pintype "power_in"))
      (node (ref "IC5") (pin "95") (pinfunction "AVDD_95") (pintype "power_in"))
      (node (ref "SP5") (pin "P$1") (pinfunction "1_P$1") (pintype "bidirectional"))
    )
    (net (code "46") (name "Net-(C5-P$1)") (class "Default")
      (node (ref "C5") (pin "+") (pinfunction "P$1_+") (pintype "passive"))
      (node (ref "U$95") (pin "P$1") (pinfunction "1_P$1") (pintype "bidirectional"))
    )
    (net (code "47") (name "Net-(C6-P$2)") (class "Default")
      (node (ref "C6") (pin "2") (pinfunction "P$2_2") (pintype "passive"))
      (node (ref "IC5") (pin "18") (pinfunction "OVDD_18") (pintype "power_in"))
      (node (ref "IC5") (pin "29") (pinfunction "OVDD_29") (pintype "power_in"))
      (node (ref "IC5") (pin "43") (pinfunction "OVDD_43") (pintype "power_in"))
      (node (ref "IC5") (pin "57") (pinfunction "OVDD_57") (pintype "power_in"))
      (node (ref "IC5") (pin "78") (pinfunction "OVDD_78") (pintype "power_in"))
      (node (ref "SP4") (pin "P$1") (pinfunction "1_P$1") (pintype "bidirectional"))
    )
    (net (code "48") (name "Net-(C7-P$2)") (class "Default")
      (node (ref "C7") (pin "2") (pinfunction "P$2_2") (pintype "passive"))
      (node (ref "IC6") (pin "7") (pinfunction "PB6(PCINT6/XTAL1/TOSC1)_7") (pintype "bidirectional"))
      (node (ref "Q1") (pin "2") (pinfunction "2_2") (pintype "passive"))
    )
    (net (code "49") (name "Net-(C8-P$2)") (class "Default")
      (node (ref "C8") (pin "2") (pinfunction "P$2_2") (pintype "passive"))
      (node (ref "IC6") (pin "8") (pinfunction "PB7(PCINT7/XTAL2/TOSC2)_8") (pintype "bidirectional"))
      (node (ref "Q1") (pin "1") (pinfunction "1_1") (pintype "passive"))
    )
    (net (code "50") (name "Net-(C9-P$1)") (class "Default")
      (node (ref "C9") (pin "1") (pinfunction "P$1_1") (pintype "passive"))
      (node (ref "IC6") (pin "4") (pinfunction "VCC_4") (pintype "power_in"))
      (node (ref "SP11") (pin "P$2") (pinfunction "2_P$2") (pintype "bidirectional"))
    )
    (net (code "51") (name "Net-(C10-P$2)") (class "Default")
      (node (ref "C10") (pin "2") (pinfunction "P$2_2") (pintype "passive"))
      (node (ref "IC4") (pin "8") (pinfunction "VCC_8") (pintype "power_in"))
      (node (ref "SP10") (pin "P$2") (pinfunction "2_P$2") (pintype "bidirectional"))
    )
    (net (code "52") (name "Net-(C11-P$1)") (class "Default")
      (node (ref "C11") (pin "1") (pinfunction "P$1_1") (pintype "passive"))
      (node (ref "IC7") (pin "17") (pinfunction "3V3OUT_17") (pintype "output"))
    )
    (net (code "53") (name "Net-(C12-P$1)") (class "Default")
      (node (ref "C12") (pin "1") (pinfunction "P$1_1") (pintype "passive"))
      (node (ref "IC7") (pin "20") (pinfunction "VCC_20") (pintype "power_in"))
      (node (ref "SP9") (pin "P$1") (pinfunction "1_P$1") (pintype "bidirectional"))
    )
    (net (code "54") (name "Net-(C13-P$2)") (class "Default")
      (node (ref "C13") (pin "2") (pinfunction "P$2_2") (pintype "passive"))
      (node (ref "IC5") (pin "97") (pinfunction "PVDD_97") (pintype "power_in"))
      (node (ref "SP2") (pin "P$1") (pinfunction "1_P$1") (pintype "bidirectional"))
    )
    (net (code "55") (name "Net-(C14-P$2)") (class "Default")
      (node (ref "C14") (pin "2") (pinfunction "P$2_2") (pintype "passive"))
      (node (ref "IC5") (pin "38") (pinfunction "DVDD_38") (pintype "power_in"))
      (node (ref "IC5") (pin "6") (pinfunction "DVDD_6") (pintype "power_in"))
      (node (ref "IC5") (pin "67") (pinfunction "DVDD_67") (pintype "power_in"))
      (node (ref "SP3") (pin "P$1") (pinfunction "1_P$1") (pintype "bidirectional"))
    )
    (net (code "56") (name "Net-(C15-P$2)") (class "Default")
      (node (ref "C15") (pin "2") (pinfunction "P$2_2") (pintype "passive"))
      (node (ref "C18") (pin "2") (pinfunction "P$2_2") (pintype "passive"))
      (node (ref "IC8") (pin "44") (pinfunction "LVDSVCC_44") (pintype "power_in"))
      (node (ref "SP17") (pin "P$1") (pinfunction "1_P$1") (pintype "bidirectional"))
    )
    (net (code "57") (name "Net-(C16-P$2)") (class "Default")
      (node (ref "C16") (pin "2") (pinfunction "P$2_2") (pintype "passive"))
      (node (ref "C17") (pin "2") (pinfunction "P$2_2") (pintype "passive"))
      (node (ref "IC8") (pin "9") (pinfunction "VCC_9") (pintype "power_in"))
      (node (ref "SP14") (pin "P$1") (pinfunction "1_P$1") (pintype "bidirectional"))
    )
    (net (code "58") (name "Net-(C19-P$2)") (class "Default")
      (node (ref "C19") (pin "2") (pinfunction "P$2_2") (pintype "passive"))
      (node (ref "C20") (pin "2") (pinfunction "P$2_2") (pintype "passive"))
      (node (ref "IC8") (pin "34") (pinfunction "PLLVCC_34") (pintype "power_in"))
      (node (ref "SP18") (pin "P$1") (pinfunction "1_P$1") (pintype "bidirectional"))
    )
    (net (code "59") (name "Net-(C21-P$2)") (class "Default")
      (node (ref "C21") (pin "2") (pinfunction "P$2_2") (pintype "passive"))
      (node (ref "IC8") (pin "26") (pinfunction "IOVCC_26") (pintype "power_in"))
      (node (ref "SP16") (pin "P$1") (pinfunction "1_P$1") (pintype "bidirectional"))
    )
    (net (code "60") (name "Net-(C22-P$2)") (class "Default")
      (node (ref "C22") (pin "2") (pinfunction "P$2_2") (pintype "passive"))
      (node (ref "IC8") (pin "1") (pinfunction "IOVCC_1") (pintype "power_in"))
      (node (ref "SP15") (pin "P$1") (pinfunction "1_P$1") (pintype "bidirectional"))
    )
    (net (code "61") (name "Net-(C23-P$1)") (class "Default")
      (node (ref "C23") (pin "1") (pinfunction "P$1_1") (pintype "passive"))
      (node (ref "IC6") (pin "6") (pinfunction "VCC_6") (pintype "power_in"))
      (node (ref "SP12") (pin "P$2") (pinfunction "2_P$2") (pintype "bidirectional"))
    )
    (net (code "62") (name "Net-(C24-P$1)") (class "Default")
      (node (ref "C24") (pin "1") (pinfunction "P$1_1") (pintype "passive"))
      (node (ref "IC6") (pin "18") (pinfunction "AVCC_18") (pintype "power_in"))
      (node (ref "SP13") (pin "P$2") (pinfunction "2_P$2") (pintype "bidirectional"))
    )
    (net (code "63") (name "Net-(CON1-1)") (class "Default")
      (node (ref "CON1") (pin "3") (pinfunction "1_3") (pintype "passive"))
      (node (ref "T1") (pin "2") (pinfunction "D_2") (pintype "passive"))
    )
    (net (code "64") (name "Net-(CON2-DETECT)") (class "Default")
      (node (ref "CON2") (pin "19") (pinfunction "DETECT_19") (pintype "bidirectional"))
      (node (ref "R7") (pin "1") (pinfunction "P$1_1") (pintype "passive"))
    )
    (net (code "65") (name "Net-(CON3-LED-A)") (class "Default")
      (node (ref "CON3") (pin "2") (pinfunction "LED-A_2") (pintype "bidirectional"))
      (node (ref "T2") (pin "2") (pinfunction "S_2") (pintype "passive"))
    )
    (net (code "66") (name "Net-(IC3-GND)") (class "Default")
      (node (ref "IC3") (pin "1") (pinfunction "GND_1") (pintype "input"))
      (node (ref "R13") (pin "1") (pinfunction "P$1_1") (pintype "passive"))
      (node (ref "R14") (pin "1") (pinfunction "P$1_1") (pintype "passive"))
    )
    (net (code "67") (name "Net-(IC5-DE)") (class "Default")
      (node (ref "IC5") (pin "46") (pinfunction "DE_46") (pintype "bidirectional"))
      (node (ref "R2") (pin "3M") (pinfunction "3M_3M") (pintype "bidirectional"))
    )
    (net (code "68") (name "Net-(IC5-HSYNC)") (class "Default")
      (node (ref "IC5") (pin "48") (pinfunction "HSYNC_48") (pintype "bidirectional"))
      (node (ref "R2") (pin "1M") (pinfunction "1M_1M") (pintype "bidirectional"))
    )
    (net (code "69") (name "Net-(IC5-ODCK)") (class "Default")
      (node (ref "IC5") (pin "44") (pinfunction "ODCK_44") (pintype "bidirectional"))
      (node (ref "R2") (pin "4M") (pinfunction "4M_4M") (pintype "bidirectional"))
    )
    (net (code "70") (name "Net-(IC5-QE0)") (class "Default")
      (node (ref "IC5") (pin "10") (pinfunction "QE0_10") (pintype "bidirectional"))
      (node (ref "R3") (pin "4M") (pinfunction "4M_4M") (pintype "bidirectional"))
    )
    (net (code "71") (name "Net-(IC5-QE1)") (class "Default")
      (node (ref "IC5") (pin "11") (pinfunction "QE1_11") (pintype "bidirectional"))
      (node (ref "R3") (pin "3M") (pinfunction "3M_3M") (pintype "bidirectional"))
    )
    (net (code "72") (name "Net-(IC5-QE2)") (class "Default")
      (node (ref "IC5") (pin "12") (pinfunction "QE2_12") (pintype "bidirectional"))
      (node (ref "R3") (pin "2M") (pinfunction "2M_2M") (pintype "bidirectional"))
    )
    (net (code "73") (name "Net-(IC5-QE3)") (class "Default")
      (node (ref "IC5") (pin "13") (pinfunction "QE3_13") (pintype "bidirectional"))
      (node (ref "R3") (pin "1M") (pinfunction "1M_1M") (pintype "bidirectional"))
    )
    (net (code "74") (name "Net-(IC5-QE4)") (class "Default")
      (node (ref "IC5") (pin "14") (pinfunction "QE4_14") (pintype "bidirectional"))
      (node (ref "R8") (pin "4M") (pinfunction "4M_4M") (pintype "bidirectional"))
    )
    (net (code "75") (name "Net-(IC5-QE5)") (class "Default")
      (node (ref "IC5") (pin "15") (pinfunction "QE5_15") (pintype "bidirectional"))
      (node (ref "R8") (pin "3M") (pinfunction "3M_3M") (pintype "bidirectional"))
    )
    (net (code "76") (name "Net-(IC5-QE6)") (class "Default")
      (node (ref "IC5") (pin "16") (pinfunction "QE6_16") (pintype "bidirectional"))
      (node (ref "R8") (pin "2M") (pinfunction "2M_2M") (pintype "bidirectional"))
    )
    (net (code "77") (name "Net-(IC5-QE7)") (class "Default")
      (node (ref "IC5") (pin "17") (pinfunction "QE7_17") (pintype "bidirectional"))
      (node (ref "R8") (pin "1M") (pinfunction "1M_1M") (pintype "bidirectional"))
    )
    (net (code "78") (name "Net-(IC5-QE8)") (class "Default")
      (node (ref "IC5") (pin "20") (pinfunction "QE8_20") (pintype "bidirectional"))
      (node (ref "R9") (pin "4M") (pinfunction "4M_4M") (pintype "bidirectional"))
    )
    (net (code "79") (name "Net-(IC5-QE9)") (class "Default")
      (node (ref "IC5") (pin "21") (pinfunction "QE9_21") (pintype "bidirectional"))
      (node (ref "R9") (pin "3M") (pinfunction "3M_3M") (pintype "bidirectional"))
    )
    (net (code "80") (name "Net-(IC5-QE10)") (class "Default")
      (node (ref "IC5") (pin "22") (pinfunction "QE10_22") (pintype "bidirectional"))
      (node (ref "R9") (pin "2M") (pinfunction "2M_2M") (pintype "bidirectional"))
    )
    (net (code "81") (name "Net-(IC5-QE11)") (class "Default")
      (node (ref "IC5") (pin "23") (pinfunction "QE11_23") (pintype "bidirectional"))
      (node (ref "R9") (pin "1M") (pinfunction "1M_1M") (pintype "bidirectional"))
    )
    (net (code "82") (name "Net-(IC5-QE12)") (class "Default")
      (node (ref "IC5") (pin "24") (pinfunction "QE12_24") (pintype "bidirectional"))
      (node (ref "R10") (pin "4M") (pinfunction "4M_4M") (pintype "bidirectional"))
    )
    (net (code "83") (name "Net-(IC5-QE13)") (class "Default")
      (node (ref "IC5") (pin "25") (pinfunction "QE13_25") (pintype "bidirectional"))
      (node (ref "R10") (pin "3M") (pinfunction "3M_3M") (pintype "bidirectional"))
    )
    (net (code "84") (name "Net-(IC5-QE14)") (class "Default")
      (node (ref "IC5") (pin "26") (pinfunction "QE14_26") (pintype "bidirectional"))
      (node (ref "R10") (pin "2M") (pinfunction "2M_2M") (pintype "bidirectional"))
    )
    (net (code "85") (name "Net-(IC5-QE15)") (class "Default")
      (node (ref "IC5") (pin "27") (pinfunction "QE15_27") (pintype "bidirectional"))
      (node (ref "R10") (pin "1M") (pinfunction "1M_1M") (pintype "bidirectional"))
    )
    (net (code "86") (name "Net-(IC5-QE16)") (class "Default")
      (node (ref "IC5") (pin "30") (pinfunction "QE16_30") (pintype "bidirectional"))
      (node (ref "R11") (pin "4M") (pinfunction "4M_4M") (pintype "bidirectional"))
    )
    (net (code "87") (name "Net-(IC5-QE17)") (class "Default")
      (node (ref "IC5") (pin "31") (pinfunction "QE17_31") (pintype "bidirectional"))
      (node (ref "R11") (pin "3M") (pinfunction "3M_3M") (pintype "bidirectional"))
    )
    (net (code "88") (name "Net-(IC5-QE18)") (class "Default")
      (node (ref "IC5") (pin "32") (pinfunction "QE18_32") (pintype "bidirectional"))
      (node (ref "R11") (pin "2M") (pinfunction "2M_2M") (pintype "bidirectional"))
    )
    (net (code "89") (name "Net-(IC5-QE19)") (class "Default")
      (node (ref "IC5") (pin "33") (pinfunction "QE19_33") (pintype "bidirectional"))
      (node (ref "R11") (pin "1M") (pinfunction "1M_1M") (pintype "bidirectional"))
    )
    (net (code "90") (name "Net-(IC5-QE20)") (class "Default")
      (node (ref "IC5") (pin "34") (pinfunction "QE20_34") (pintype "bidirectional"))
      (node (ref "R12") (pin "4M") (pinfunction "4M_4M") (pintype "bidirectional"))
    )
    (net (code "91") (name "Net-(IC5-QE21)") (class "Default")
      (node (ref "IC5") (pin "35") (pinfunction "QE21_35") (pintype "bidirectional"))
      (node (ref "R12") (pin "3M") (pinfunction "3M_3M") (pintype "bidirectional"))
    )
    (net (code "92") (name "Net-(IC5-QE22)") (class "Default")
      (node (ref "IC5") (pin "36") (pinfunction "QE22_36") (pintype "bidirectional"))
      (node (ref "R12") (pin "2M") (pinfunction "2M_2M") (pintype "bidirectional"))
    )
    (net (code "93") (name "Net-(IC5-QE23)") (class "Default")
      (node (ref "IC5") (pin "37") (pinfunction "QE23_37") (pintype "bidirectional"))
      (node (ref "R12") (pin "1M") (pinfunction "1M_1M") (pintype "bidirectional"))
    )
    (net (code "94") (name "Net-(IC5-VSYNC)") (class "Default")
      (node (ref "IC5") (pin "47") (pinfunction "VSYNC_47") (pintype "bidirectional"))
      (node (ref "R2") (pin "2M") (pinfunction "2M_2M") (pintype "bidirectional"))
    )
    (net (code "95") (name "Net-(R1-P$2)") (class "Default")
      (node (ref "D1") (pin "A") (pinfunction "A_A") (pintype "passive"))
      (node (ref "R1") (pin "2") (pinfunction "P$2_2") (pintype "passive"))
      (node (ref "T1") (pin "1") (pinfunction "G_1") (pintype "passive"))
    )
    (net (code "96") (name "Net-(R20-P$1)") (class "Default")
      (node (ref "R20") (pin "1") (pinfunction "P$1_1") (pintype "passive"))
      (node (ref "R21") (pin "1") (pinfunction "P$1_1") (pintype "passive"))
      (node (ref "T2") (pin "3") (pinfunction "D_3") (pintype "passive"))
    )
    (net (code "97") (name "RGB_DE") (class "Default")
      (node (ref "CON3") (pin "34") (pinfunction "DEN_34") (pintype "bidirectional"))
      (node (ref "IC8") (pin "30") (pinfunction "D26_30") (pintype "bidirectional"))
      (node (ref "R2") (pin "3P") (pinfunction "3P_3P") (pintype "bidirectional"))
    )
    (net (code "98") (name "RGB_DISP") (class "Default")
      (node (ref "CON3") (pin "31") (pinfunction "DISP_31") (pintype "bidirectional"))
      (node (ref "JP3") (pin "2") (pinfunction "2_2") (pintype "passive"))
      (node (ref "R15") (pin "1") (pinfunction "P$1_1") (pintype "passive"))
    )
    (net (code "99") (name "RGB_EVEN_B0") (class "Default")
      (node (ref "CON3") (pin "21") (pinfunction "B0_21") (pintype "bidirectional"))
      (node (ref "IC8") (pin "15") (pinfunction "D15_15") (pintype "bidirectional"))
      (node (ref "R3") (pin "4P") (pinfunction "4P_4P") (pintype "bidirectional"))
    )
    (net (code "100") (name "RGB_EVEN_B1") (class "Default")
      (node (ref "CON3") (pin "22") (pinfunction "B1_22") (pintype "bidirectional"))
      (node (ref "IC8") (pin "19") (pinfunction "D18_19") (pintype "bidirectional"))
      (node (ref "R3") (pin "3P") (pinfunction "3P_3P") (pintype "bidirectional"))
    )
    (net (code "101") (name "RGB_EVEN_B2") (class "Default")
      (node (ref "CON3") (pin "23") (pinfunction "B2_23") (pintype "bidirectional"))
      (node (ref "IC8") (pin "20") (pinfunction "D19_20") (pintype "bidirectional"))
      (node (ref "R3") (pin "2P") (pinfunction "2P_2P") (pintype "bidirectional"))
    )
    (net (code "102") (name "RGB_EVEN_B3") (class "Default")
      (node (ref "CON3") (pin "24") (pinfunction "B3_24") (pintype "bidirectional"))
      (node (ref "IC8") (pin "22") (pinfunction "D20_22") (pintype "bidirectional"))
      (node (ref "R3") (pin "1P") (pinfunction "1P_1P") (pintype "bidirectional"))
    )
    (net (code "103") (name "RGB_EVEN_B4") (class "Default")
      (node (ref "CON3") (pin "25") (pinfunction "B4_25") (pintype "bidirectional"))
      (node (ref "IC8") (pin "23") (pinfunction "D21_23") (pintype "bidirectional"))
      (node (ref "R8") (pin "4P") (pinfunction "4P_4P") (pintype "bidirectional"))
    )
    (net (code "104") (name "RGB_EVEN_B5") (class "Default")
      (node (ref "CON3") (pin "26") (pinfunction "B5_26") (pintype "bidirectional"))
      (node (ref "IC8") (pin "24") (pinfunction "D22_24") (pintype "bidirectional"))
      (node (ref "R8") (pin "3P") (pinfunction "3P_3P") (pintype "bidirectional"))
    )
    (net (code "105") (name "RGB_EVEN_B6") (class "Default")
      (node (ref "CON3") (pin "27") (pinfunction "B6_27") (pintype "bidirectional"))
      (node (ref "IC8") (pin "16") (pinfunction "D16_16") (pintype "bidirectional"))
      (node (ref "R8") (pin "2P") (pinfunction "2P_2P") (pintype "bidirectional"))
    )
    (net (code "106") (name "RGB_EVEN_B7") (class "Default")
      (node (ref "CON3") (pin "28") (pinfunction "B7_28") (pintype "bidirectional"))
      (node (ref "IC8") (pin "18") (pinfunction "D17_18") (pintype "bidirectional"))
      (node (ref "R8") (pin "1P") (pinfunction "1P_1P") (pintype "bidirectional"))
    )
    (net (code "107") (name "RGB_EVEN_G0") (class "Default")
      (node (ref "CON3") (pin "13") (pinfunction "G0_13") (pintype "bidirectional"))
      (node (ref "IC8") (pin "4") (pinfunction "D7_4") (pintype "bidirectional"))
      (node (ref "R9") (pin "4P") (pinfunction "4P_4P") (pintype "bidirectional"))
    )
    (net (code "108") (name "RGB_EVEN_G1") (class "Default")
      (node (ref "CON3") (pin "14") (pinfunction "G1_14") (pintype "bidirectional"))
      (node (ref "IC8") (pin "6") (pinfunction "D8_6") (pintype "bidirectional"))
      (node (ref "R9") (pin "3P") (pinfunction "3P_3P") (pintype "bidirectional"))
    )
    (net (code "109") (name "RGB_EVEN_G2") (class "Default")
      (node (ref "CON3") (pin "15") (pinfunction "G2_15") (pintype "bidirectional"))
      (node (ref "IC8") (pin "7") (pinfunction "D9_7") (pintype "bidirectional"))
      (node (ref "R9") (pin "2P") (pinfunction "2P_2P") (pintype "bidirectional"))
    )
    (net (code "110") (name "RGB_EVEN_G3") (class "Default")
      (node (ref "CON3") (pin "16") (pinfunction "G3_16") (pintype "bidirectional"))
      (node (ref "IC8") (pin "11") (pinfunction "D12_11") (pintype "bidirectional"))
      (node (ref "R9") (pin "1P") (pinfunction "1P_1P") (pintype "bidirectional"))
    )
    (net (code "111") (name "RGB_EVEN_G4") (class "Default")
      (node (ref "CON3") (pin "17") (pinfunction "G4_17") (pintype "bidirectional"))
      (node (ref "IC8") (pin "12") (pinfunction "D13_12") (pintype "bidirectional"))
      (node (ref "R10") (pin "4P") (pinfunction "4P_4P") (pintype "bidirectional"))
    )
    (net (code "112") (name "RGB_EVEN_G5") (class "Default")
      (node (ref "CON3") (pin "18") (pinfunction "G5_18") (pintype "bidirectional"))
      (node (ref "IC8") (pin "14") (pinfunction "D14_14") (pintype "bidirectional"))
      (node (ref "R10") (pin "3P") (pinfunction "3P_3P") (pintype "bidirectional"))
    )
    (net (code "113") (name "RGB_EVEN_G6") (class "Default")
      (node (ref "CON3") (pin "19") (pinfunction "G6_19") (pintype "bidirectional"))
      (node (ref "IC8") (pin "8") (pinfunction "D10_8") (pintype "bidirectional"))
      (node (ref "R10") (pin "2P") (pinfunction "2P_2P") (pintype "bidirectional"))
    )
    (net (code "114") (name "RGB_EVEN_G7") (class "Default")
      (node (ref "CON3") (pin "20") (pinfunction "G7_20") (pintype "bidirectional"))
      (node (ref "IC8") (pin "10") (pinfunction "D11_10") (pintype "bidirectional"))
      (node (ref "R10") (pin "1P") (pinfunction "1P_1P") (pintype "bidirectional"))
    )
    (net (code "115") (name "RGB_EVEN_R0") (class "Default")
      (node (ref "CON3") (pin "5") (pinfunction "R0_5") (pintype "bidirectional"))
      (node (ref "IC8") (pin "51") (pinfunction "D0_51") (pintype "bidirectional"))
      (node (ref "R11") (pin "4P") (pinfunction "4P_4P") (pintype "bidirectional"))
    )
    (net (code "116") (name "RGB_EVEN_R1") (class "Default")
      (node (ref "CON3") (pin "6") (pinfunction "R1_6") (pintype "bidirectional"))
      (node (ref "IC8") (pin "52") (pinfunction "D1_52") (pintype "bidirectional"))
      (node (ref "R11") (pin "3P") (pinfunction "3P_3P") (pintype "bidirectional"))
    )
    (net (code "117") (name "RGB_EVEN_R2") (class "Default")
      (node (ref "CON3") (pin "7") (pinfunction "R2_7") (pintype "bidirectional"))
      (node (ref "IC8") (pin "54") (pinfunction "D2_54") (pintype "bidirectional"))
      (node (ref "R11") (pin "2P") (pinfunction "2P_2P") (pintype "bidirectional"))
    )
    (net (code "118") (name "RGB_EVEN_R3") (class "Default")
      (node (ref "CON3") (pin "8") (pinfunction "R3_8") (pintype "bidirectional"))
      (node (ref "IC8") (pin "55") (pinfunction "D3_55") (pintype "bidirectional"))
      (node (ref "R11") (pin "1P") (pinfunction "1P_1P") (pintype "bidirectional"))
    )
    (net (code "119") (name "RGB_EVEN_R4") (class "Default")
      (node (ref "CON3") (pin "9") (pinfunction "R4_9") (pintype "bidirectional"))
      (node (ref "IC8") (pin "56") (pinfunction "D4_56") (pintype "bidirectional"))
      (node (ref "R12") (pin "4P") (pinfunction "4P_4P") (pintype "bidirectional"))
    )
    (net (code "120") (name "RGB_EVEN_R5") (class "Default")
      (node (ref "CON3") (pin "10") (pinfunction "R5_10") (pintype "bidirectional"))
      (node (ref "IC8") (pin "3") (pinfunction "D6_3") (pintype "bidirectional"))
      (node (ref "R12") (pin "3P") (pinfunction "3P_3P") (pintype "bidirectional"))
    )
    (net (code "121") (name "RGB_EVEN_R6") (class "Default")
      (node (ref "CON3") (pin "11") (pinfunction "R6_11") (pintype "bidirectional"))
      (node (ref "IC8") (pin "50") (pinfunction "D27_50") (pintype "bidirectional"))
      (node (ref "R12") (pin "2P") (pinfunction "2P_2P") (pintype "bidirectional"))
    )
    (net (code "122") (name "RGB_EVEN_R7") (class "Default")
      (node (ref "CON3") (pin "12") (pinfunction "R7_12") (pintype "bidirectional"))
      (node (ref "IC8") (pin "2") (pinfunction "D5_2") (pintype "bidirectional"))
      (node (ref "R12") (pin "1P") (pinfunction "1P_1P") (pintype "bidirectional"))
    )
    (net (code "123") (name "RGB_HSYNC") (class "Default")
      (node (ref "CON3") (pin "32") (pinfunction "HSYNC_32") (pintype "bidirectional"))
      (node (ref "IC8") (pin "27") (pinfunction "D24_27") (pintype "bidirectional"))
      (node (ref "R2") (pin "2P") (pinfunction "2P_2P") (pintype "bidirectional"))
    )
    (net (code "124") (name "RGB_ODCK") (class "Default")
      (node (ref "CON3") (pin "30") (pinfunction "CLK_30") (pintype "bidirectional"))
      (node (ref "IC8") (pin "31") (pinfunction "CLKIN_31") (pintype "bidirectional"))
      (node (ref "R2") (pin "4P") (pinfunction "4P_4P") (pintype "bidirectional"))
    )
    (net (code "125") (name "RGB_PWM") (class "Default")
      (node (ref "JP4") (pin "3") (pinfunction "3_3") (pintype "passive"))
      (node (ref "JP6") (pin "1") (pinfunction "1_1") (pintype "passive"))
    )
    (net (code "126") (name "RGB_PWM_EN") (class "Default")
      (node (ref "JP4") (pin "2") (pinfunction "2_2") (pintype "passive"))
      (node (ref "T2") (pin "1") (pinfunction "G_1") (pintype "passive"))
    )
    (net (code "127") (name "RGB_VSYNC") (class "Default")
      (node (ref "CON3") (pin "33") (pinfunction "VSYNC_33") (pintype "bidirectional"))
      (node (ref "IC8") (pin "28") (pinfunction "D25_28") (pintype "bidirectional"))
      (node (ref "R2") (pin "1P") (pinfunction "1P_1P") (pintype "bidirectional"))
    )
    (net (code "128") (name "USB_D+") (class "Default")
      (node (ref "CON4") (pin "3") (pinfunction "D+_3") (pintype "bidirectional"))
      (node (ref "IC7") (pin "16") (pinfunction "USBDM_16") (pintype "bidirectional"))
    )
    (net (code "129") (name "USB_D-") (class "Default")
      (node (ref "CON4") (pin "2") (pinfunction "D-_2") (pintype "bidirectional"))
      (node (ref "IC7") (pin "15") (pinfunction "USBDP_15") (pintype "bidirectional"))
    )
    (net (code "130") (name "unconnected-(CON2-CEC-Pad13)") (class "Default")
      (node (ref "CON2") (pin "13") (pinfunction "CEC_13") (pintype "bidirectional"))
    )
    (net (code "131") (name "unconnected-(CON2-NC-Pad14)") (class "Default")
      (node (ref "CON2") (pin "14") (pinfunction "NC_14") (pintype "bidirectional"))
    )
    (net (code "132") (name "unconnected-(CON3-NC-Pad35)") (class "Default")
      (node (ref "CON3") (pin "35") (pinfunction "NC_35") (pintype "bidirectional"))
    )
    (net (code "133") (name "unconnected-(CON3-XL-Pad39)") (class "Default")
      (node (ref "CON3") (pin "39") (pinfunction "XL_39") (pintype "bidirectional"))
    )
    (net (code "134") (name "unconnected-(CON3-XR-Pad37)") (class "Default")
      (node (ref "CON3") (pin "37") (pinfunction "XR_37") (pintype "bidirectional"))
    )
    (net (code "135") (name "unconnected-(CON3-YD-Pad38)") (class "Default")
      (node (ref "CON3") (pin "38") (pinfunction "YD_38") (pintype "bidirectional"))
    )
    (net (code "136") (name "unconnected-(CON3-YU-Pad40)") (class "Default")
      (node (ref "CON3") (pin "40") (pinfunction "YU_40") (pintype "bidirectional"))
    )
    (net (code "137") (name "unconnected-(CON4-ID-Pad4)") (class "Default")
      (node (ref "CON4") (pin "4") (pinfunction "ID_4") (pintype "bidirectional"))
    )
    (net (code "138") (name "unconnected-(CON6-NC-Pad27)") (class "Default")
      (node (ref "CON6") (pin "27") (pinfunction "NC_27") (pintype "bidirectional"))
    )
    (net (code "139") (name "unconnected-(CON6-TP-Pad22)") (class "Default")
      (node (ref "CON6") (pin "22") (pinfunction "TP_22") (pintype "bidirectional"))
    )
    (net (code "140") (name "unconnected-(CON6-TP-Pad23)") (class "Default")
      (node (ref "CON6") (pin "23") (pinfunction "TP_23") (pintype "bidirectional"))
    )
    (net (code "141") (name "unconnected-(IC1-EN-Pad5)") (class "Default")
      (node (ref "IC1") (pin "5") (pinfunction "EN_5") (pintype "bidirectional"))
    )
    (net (code "142") (name "unconnected-(IC1-PG-Pad4)") (class "Default")
      (node (ref "IC1") (pin "4") (pinfunction "PG_4") (pintype "bidirectional"))
    )
    (net (code "143") (name "unconnected-(IC2-EN-Pad5)") (class "Default")
      (node (ref "IC2") (pin "5") (pinfunction "EN_5") (pintype "bidirectional"))
    )
    (net (code "144") (name "unconnected-(IC2-PG-Pad4)") (class "Default")
      (node (ref "IC2") (pin "4") (pinfunction "PG_4") (pintype "bidirectional"))
    )
    (net (code "145") (name "unconnected-(IC5-CTL1-Pad40)") (class "Default")
      (node (ref "IC5") (pin "40") (pinfunction "CTL1_40") (pintype "bidirectional"))
    )
    (net (code "146") (name "unconnected-(IC5-CTL2-Pad41)") (class "Default")
      (node (ref "IC5") (pin "41") (pinfunction "CTL2_41") (pintype "bidirectional"))
    )
    (net (code "147") (name "unconnected-(IC5-CTL3-Pad42)") (class "Default")
      (node (ref "IC5") (pin "42") (pinfunction "CTL3_42") (pintype "bidirectional"))
    )
    (net (code "148") (name "unconnected-(IC5-EXT_RES-Pad96)") (class "Default")
      (node (ref "IC5") (pin "96") (pinfunction "EXT_RES_96") (pintype "bidirectional"))
    )
    (net (code "149") (name "unconnected-(IC5-QO0-Pad49)") (class "Default")
      (node (ref "IC5") (pin "49") (pinfunction "QO0_49") (pintype "bidirectional"))
    )
    (net (code "150") (name "unconnected-(IC5-QO1-Pad50)") (class "Default")
      (node (ref "IC5") (pin "50") (pinfunction "QO1_50") (pintype "bidirectional"))
    )
    (net (code "151") (name "unconnected-(IC5-QO2-Pad51)") (class "Default")
      (node (ref "IC5") (pin "51") (pinfunction "QO2_51") (pintype "bidirectional"))
    )
    (net (code "152") (name "unconnected-(IC5-QO3-Pad52)") (class "Default")
      (node (ref "IC5") (pin "52") (pinfunction "QO3_52") (pintype "bidirectional"))
    )
    (net (code "153") (name "unconnected-(IC5-QO4-Pad53)") (class "Default")
      (node (ref "IC5") (pin "53") (pinfunction "QO4_53") (pintype "bidirectional"))
    )
    (net (code "154") (name "unconnected-(IC5-QO5-Pad54)") (class "Default")
      (node (ref "IC5") (pin "54") (pinfunction "QO5_54") (pintype "bidirectional"))
    )
    (net (code "155") (name "unconnected-(IC5-QO6-Pad55)") (class "Default")
      (node (ref "IC5") (pin "55") (pinfunction "QO6_55") (pintype "bidirectional"))
    )
    (net (code "156") (name "unconnected-(IC5-QO7-Pad56)") (class "Default")
      (node (ref "IC5") (pin "56") (pinfunction "QO7_56") (pintype "bidirectional"))
    )
    (net (code "157") (name "unconnected-(IC5-QO8-Pad59)") (class "Default")
      (node (ref "IC5") (pin "59") (pinfunction "QO8_59") (pintype "bidirectional"))
    )
    (net (code "158") (name "unconnected-(IC5-QO9-Pad60)") (class "Default")
      (node (ref "IC5") (pin "60") (pinfunction "QO9_60") (pintype "bidirectional"))
    )
    (net (code "159") (name "unconnected-(IC5-QO10-Pad61)") (class "Default")
      (node (ref "IC5") (pin "61") (pinfunction "QO10_61") (pintype "bidirectional"))
    )
    (net (code "160") (name "unconnected-(IC5-QO11-Pad62)") (class "Default")
      (node (ref "IC5") (pin "62") (pinfunction "QO11_62") (pintype "bidirectional"))
    )
    (net (code "161") (name "unconnected-(IC5-QO12-Pad63)") (class "Default")
      (node (ref "IC5") (pin "63") (pinfunction "QO12_63") (pintype "bidirectional"))
    )
    (net (code "162") (name "unconnected-(IC5-QO13-Pad64)") (class "Default")
      (node (ref "IC5") (pin "64") (pinfunction "QO13_64") (pintype "bidirectional"))
    )
    (net (code "163") (name "unconnected-(IC5-QO14-Pad65)") (class "Default")
      (node (ref "IC5") (pin "65") (pinfunction "QO14_65") (pintype "bidirectional"))
    )
    (net (code "164") (name "unconnected-(IC5-QO15-Pad66)") (class "Default")
      (node (ref "IC5") (pin "66") (pinfunction "QO15_66") (pintype "bidirectional"))
    )
    (net (code "165") (name "unconnected-(IC5-QO16-Pad69)") (class "Default")
      (node (ref "IC5") (pin "69") (pinfunction "QO16_69") (pintype "bidirectional"))
    )
    (net (code "166") (name "unconnected-(IC5-QO17-Pad70)") (class "Default")
      (node (ref "IC5") (pin "70") (pinfunction "QO17_70") (pintype "bidirectional"))
    )
    (net (code "167") (name "unconnected-(IC5-QO18-Pad71)") (class "Default")
      (node (ref "IC5") (pin "71") (pinfunction "QO18_71") (pintype "bidirectional"))
    )
    (net (code "168") (name "unconnected-(IC5-QO19-Pad72)") (class "Default")
      (node (ref "IC5") (pin "72") (pinfunction "QO19_72") (pintype "bidirectional"))
    )
    (net (code "169") (name "unconnected-(IC5-QO20-Pad73)") (class "Default")
      (node (ref "IC5") (pin "73") (pinfunction "QO20_73") (pintype "bidirectional"))
    )
    (net (code "170") (name "unconnected-(IC5-QO21-Pad74)") (class "Default")
      (node (ref "IC5") (pin "74") (pinfunction "QO21_74") (pintype "bidirectional"))
    )
    (net (code "171") (name "unconnected-(IC5-QO22-Pad75)") (class "Default")
      (node (ref "IC5") (pin "75") (pinfunction "QO22_75") (pintype "bidirectional"))
    )
    (net (code "172") (name "unconnected-(IC5-QO23-Pad77)") (class "Default")
      (node (ref "IC5") (pin "77") (pinfunction "QO23_77") (pintype "bidirectional"))
    )
    (net (code "173") (name "unconnected-(IC5-SCDT-Pad8)") (class "Default")
      (node (ref "IC5") (pin "8") (pinfunction "SCDT_8") (pintype "bidirectional"))
    )
    (net (code "174") (name "unconnected-(IC5-~{PDO}-Pad9)") (class "Default")
      (node (ref "IC5") (pin "9") (pinfunction "~{PDO}_9") (pintype "bidirectional"))
    )
    (net (code "175") (name "unconnected-(IC5-~{PD}-Pad2)") (class "Default")
      (node (ref "IC5") (pin "2") (pinfunction "~{PD}_2") (pintype "bidirectional"))
    )
    (net (code "176") (name "unconnected-(IC6-(PCINT18{slash}INT0)PD2-Pad32)") (class "Default")
      (node (ref "IC6") (pin "32") (pinfunction "(PCINT18/INT0)PD2_32") (pintype "bidirectional"))
    )
    (net (code "177") (name "unconnected-(IC6-(PCINT19{slash}OC2B{slash}INT1)PD3-Pad1)") (class "Default")
      (node (ref "IC6") (pin "1") (pinfunction "(PCINT19/OC2B/INT1)PD3_1") (pintype "bidirectional"))
    )
    (net (code "178") (name "unconnected-(IC6-(PCINT20{slash}XCK{slash}T0)PD4-Pad2)") (class "Default")
      (node (ref "IC6") (pin "2") (pinfunction "(PCINT20/XCK/T0)PD4_2") (pintype "bidirectional"))
    )
    (net (code "179") (name "unconnected-(IC6-(PCINT21{slash}OC0B{slash}T1)PD5-Pad9)") (class "Default")
      (node (ref "IC6") (pin "9") (pinfunction "(PCINT21/OC0B/T1)PD5_9") (pintype "bidirectional"))
    )
    (net (code "180") (name "unconnected-(IC6-(PCINT22{slash}OC0A{slash}AIN0)PD6-Pad10)") (class "Default")
      (node (ref "IC6") (pin "10") (pinfunction "(PCINT22/OC0A/AIN0)PD6_10") (pintype "bidirectional"))
    )
    (net (code "181") (name "unconnected-(IC6-(PCINT23{slash}AIN1)PD7-Pad11)") (class "Default")
      (node (ref "IC6") (pin "11") (pinfunction "(PCINT23/AIN1)PD7_11") (pintype "bidirectional"))
    )
    (net (code "182") (name "unconnected-(IC6-ADC6-Pad19)") (class "Default")
      (node (ref "IC6") (pin "19") (pinfunction "ADC6_19") (pintype "bidirectional"))
    )
    (net (code "183") (name "unconnected-(IC6-ADC7-Pad22)") (class "Default")
      (node (ref "IC6") (pin "22") (pinfunction "ADC7_22") (pintype "bidirectional"))
    )
    (net (code "184") (name "unconnected-(IC6-PB0(PCINT0{slash}CLKO{slash}ICP1)-Pad12)") (class "Default")
      (node (ref "IC6") (pin "12") (pinfunction "PB0(PCINT0/CLKO/ICP1)_12") (pintype "bidirectional"))
    )
    (net (code "185") (name "unconnected-(IC6-PB2(SS{slash}OC1B{slash}PCINT2)-Pad14)") (class "Default")
      (node (ref "IC6") (pin "14") (pinfunction "PB2(SS/OC1B/PCINT2)_14") (pintype "bidirectional"))
    )
    (net (code "186") (name "unconnected-(IC6-PC1(ADC1{slash}PCINT9)-Pad24)") (class "Default")
      (node (ref "IC6") (pin "24") (pinfunction "PC1(ADC1/PCINT9)_24") (pintype "bidirectional"))
    )
    (net (code "187") (name "unconnected-(IC6-PC2(ADC2{slash}PCINT10)-Pad25)") (class "Default")
      (node (ref "IC6") (pin "25") (pinfunction "PC2(ADC2/PCINT10)_25") (pintype "bidirectional"))
    )
    (net (code "188") (name "unconnected-(IC6-PC3(ADC3{slash}PCINT11)-Pad26)") (class "Default")
      (node (ref "IC6") (pin "26") (pinfunction "PC3(ADC3/PCINT11)_26") (pintype "bidirectional"))
    )
    (net (code "189") (name "unconnected-(IC7-CBUS0-Pad23)") (class "Default")
      (node (ref "IC7") (pin "23") (pinfunction "CBUS0_23") (pintype "bidirectional"))
    )
    (net (code "190") (name "unconnected-(IC7-CBUS1-Pad22)") (class "Default")
      (node (ref "IC7") (pin "22") (pinfunction "CBUS1_22") (pintype "bidirectional"))
    )
    (net (code "191") (name "unconnected-(IC7-CBUS2-Pad13)") (class "Default")
      (node (ref "IC7") (pin "13") (pinfunction "CBUS2_13") (pintype "bidirectional"))
    )
    (net (code "192") (name "unconnected-(IC7-CBUS3-Pad14)") (class "Default")
      (node (ref "IC7") (pin "14") (pinfunction "CBUS3_14") (pintype "bidirectional"))
    )
    (net (code "193") (name "unconnected-(IC7-CBUS4-Pad12)") (class "Default")
      (node (ref "IC7") (pin "12") (pinfunction "CBUS4_12") (pintype "bidirectional"))
    )
    (net (code "194") (name "unconnected-(IC7-OSCI-Pad27)") (class "Default")
      (node (ref "IC7") (pin "27") (pinfunction "OSCI_27") (pintype "input"))
    )
    (net (code "195") (name "unconnected-(IC7-OSCO-Pad28)") (class "Default")
      (node (ref "IC7") (pin "28") (pinfunction "OSCO_28") (pintype "output"))
    )
    (net (code "196") (name "unconnected-(IC7-~{CTS}-Pad11)") (class "Default")
      (node (ref "IC7") (pin "11") (pinfunction "~{CTS}_11") (pintype "input"))
    )
    (net (code "197") (name "unconnected-(IC7-~{DCD}-Pad10)") (class "Default")
      (node (ref "IC7") (pin "10") (pinfunction "~{DCD}_10") (pintype "input"))
    )
    (net (code "198") (name "unconnected-(IC7-~{DSR}-Pad9)") (class "Default")
      (node (ref "IC7") (pin "9") (pinfunction "~{DSR}_9") (pintype "input"))
    )
    (net (code "199") (name "unconnected-(IC7-~{DTR}-Pad2)") (class "Default")
      (node (ref "IC7") (pin "2") (pinfunction "~{DTR}_2") (pintype "output"))
    )
    (net (code "200") (name "unconnected-(IC7-~{RI}-Pad6)") (class "Default")
      (node (ref "IC7") (pin "6") (pinfunction "~{RI}_6") (pintype "input"))
    )
    (net (code "201") (name "unconnected-(IC7-~{RTS}-Pad3)") (class "Default")
      (node (ref "IC7") (pin "3") (pinfunction "~{RTS}_3") (pintype "output"))
    )
    (net (code "202") (name "unconnected-(IC8-CLKSEL-Pad17)") (class "Default")
      (node (ref "IC8") (pin "17") (pinfunction "CLKSEL_17") (pintype "bidirectional"))
    )
    (net (code "203") (name "unconnected-(IC8-~{SHTDN}-Pad32)") (class "Default")
      (node (ref "IC8") (pin "32") (pinfunction "~{SHTDN}_32") (pintype "bidirectional"))
    )
  )
)
